# SDA381V5.net
KiCad netlist of a schematic drawn in EAGLE
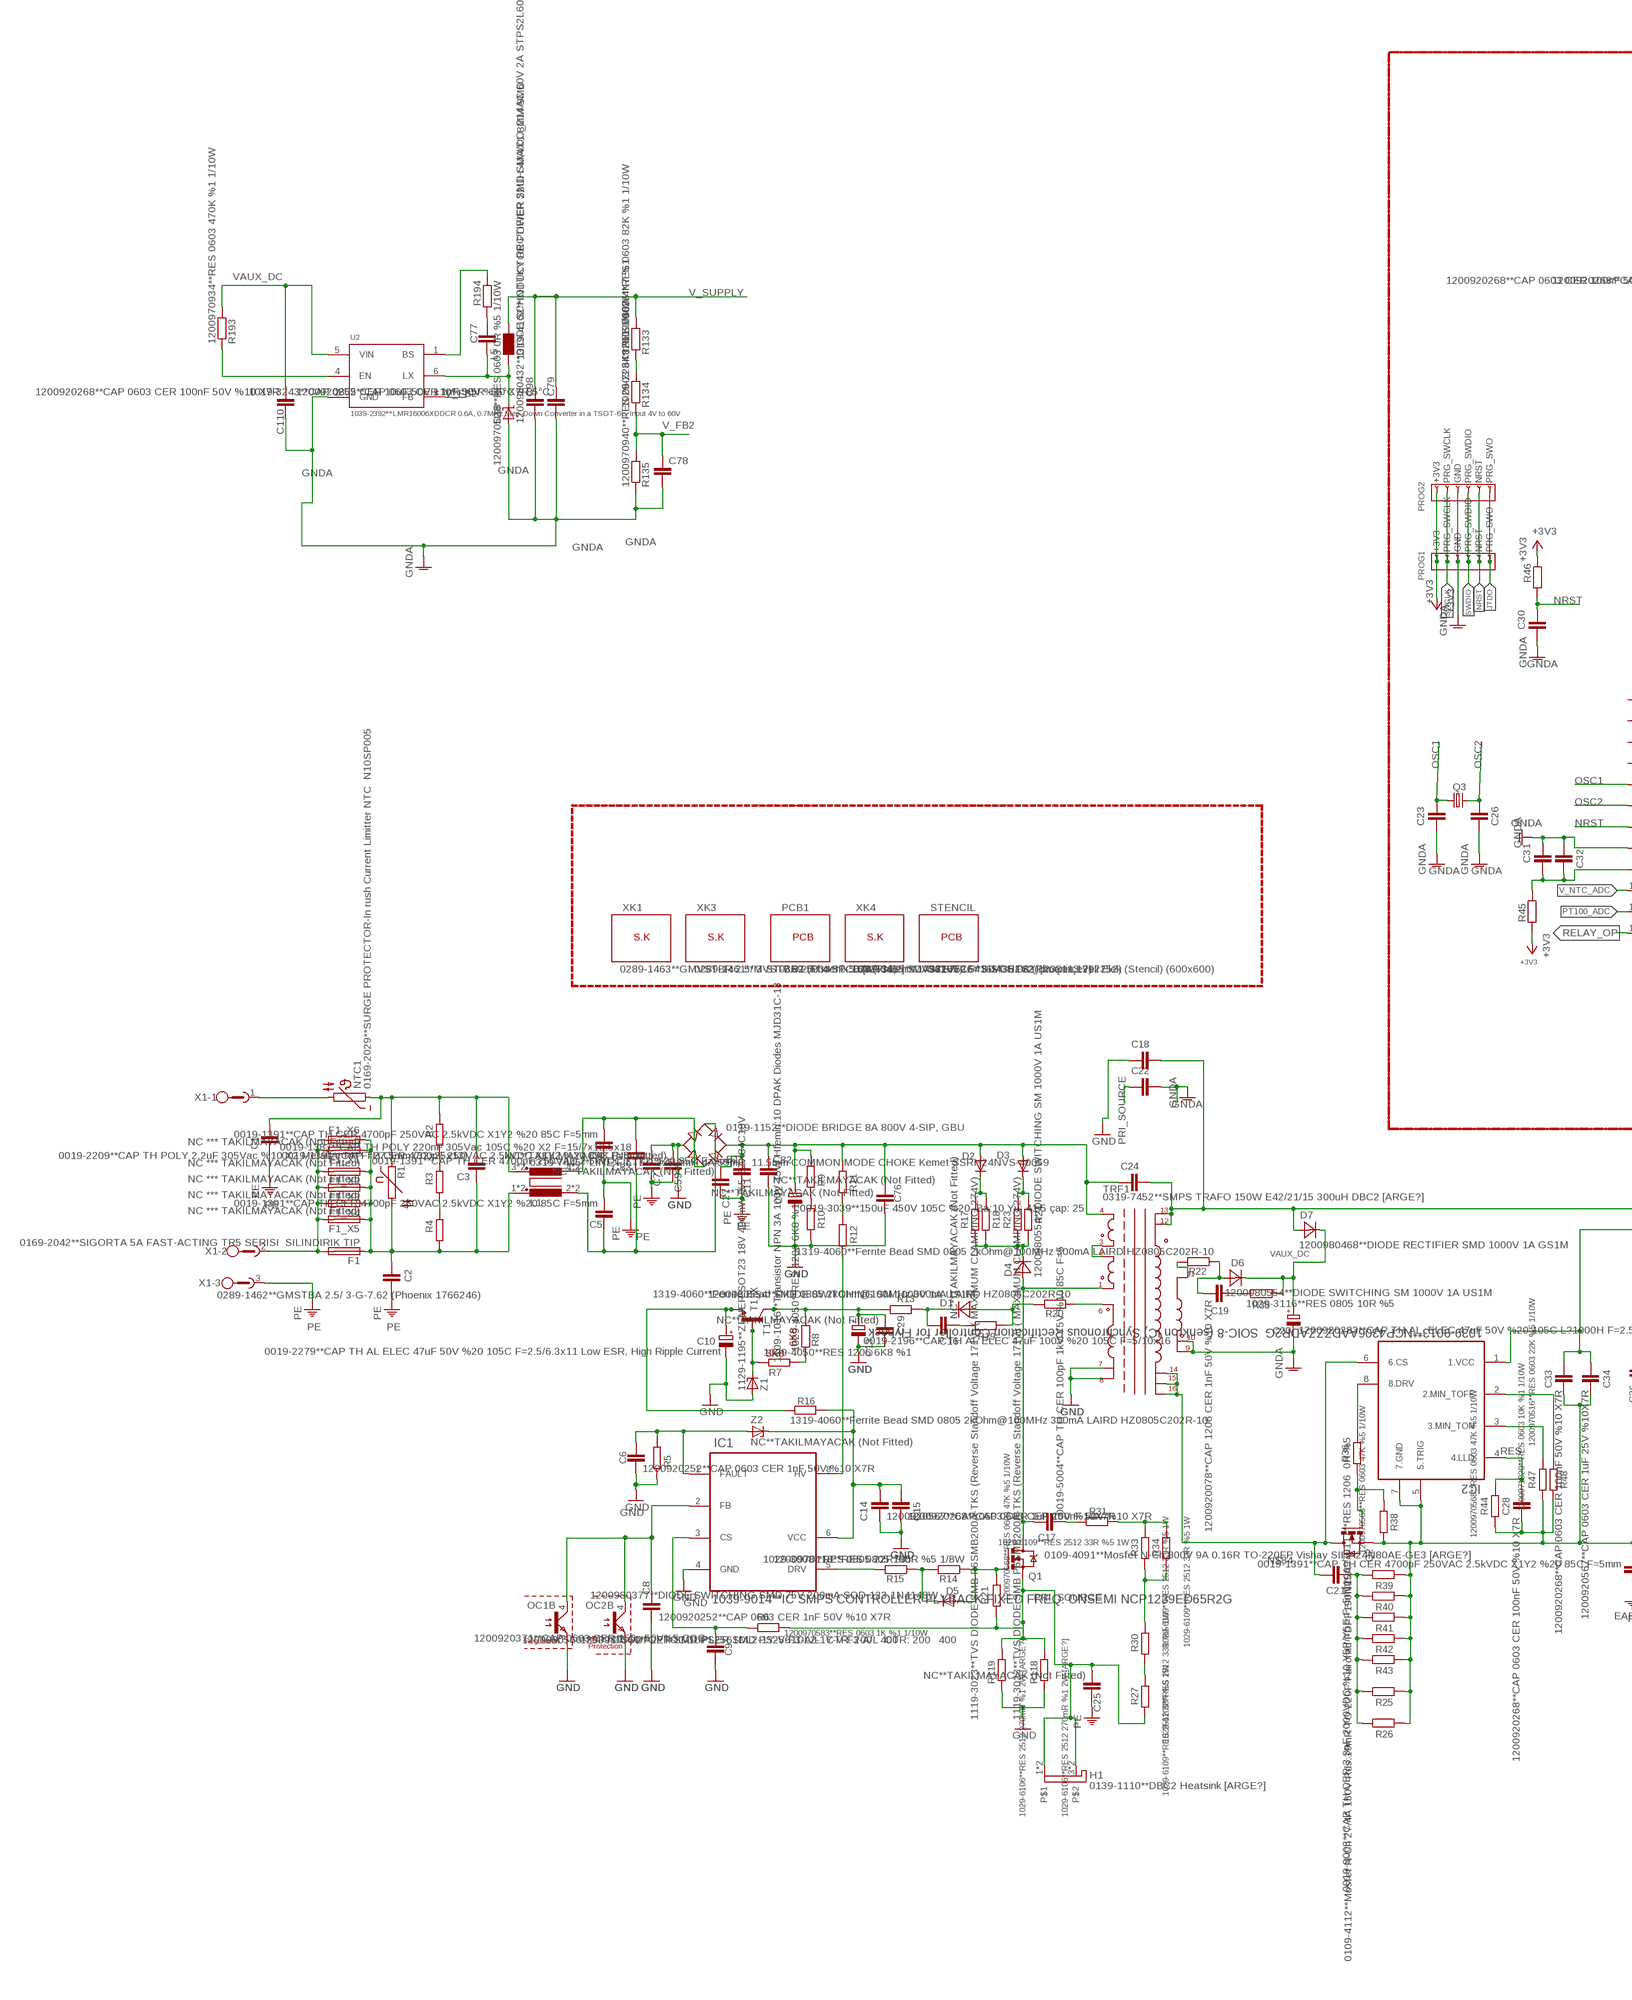
[diagram p0: schematic, sheet 1, part 1 of 2]
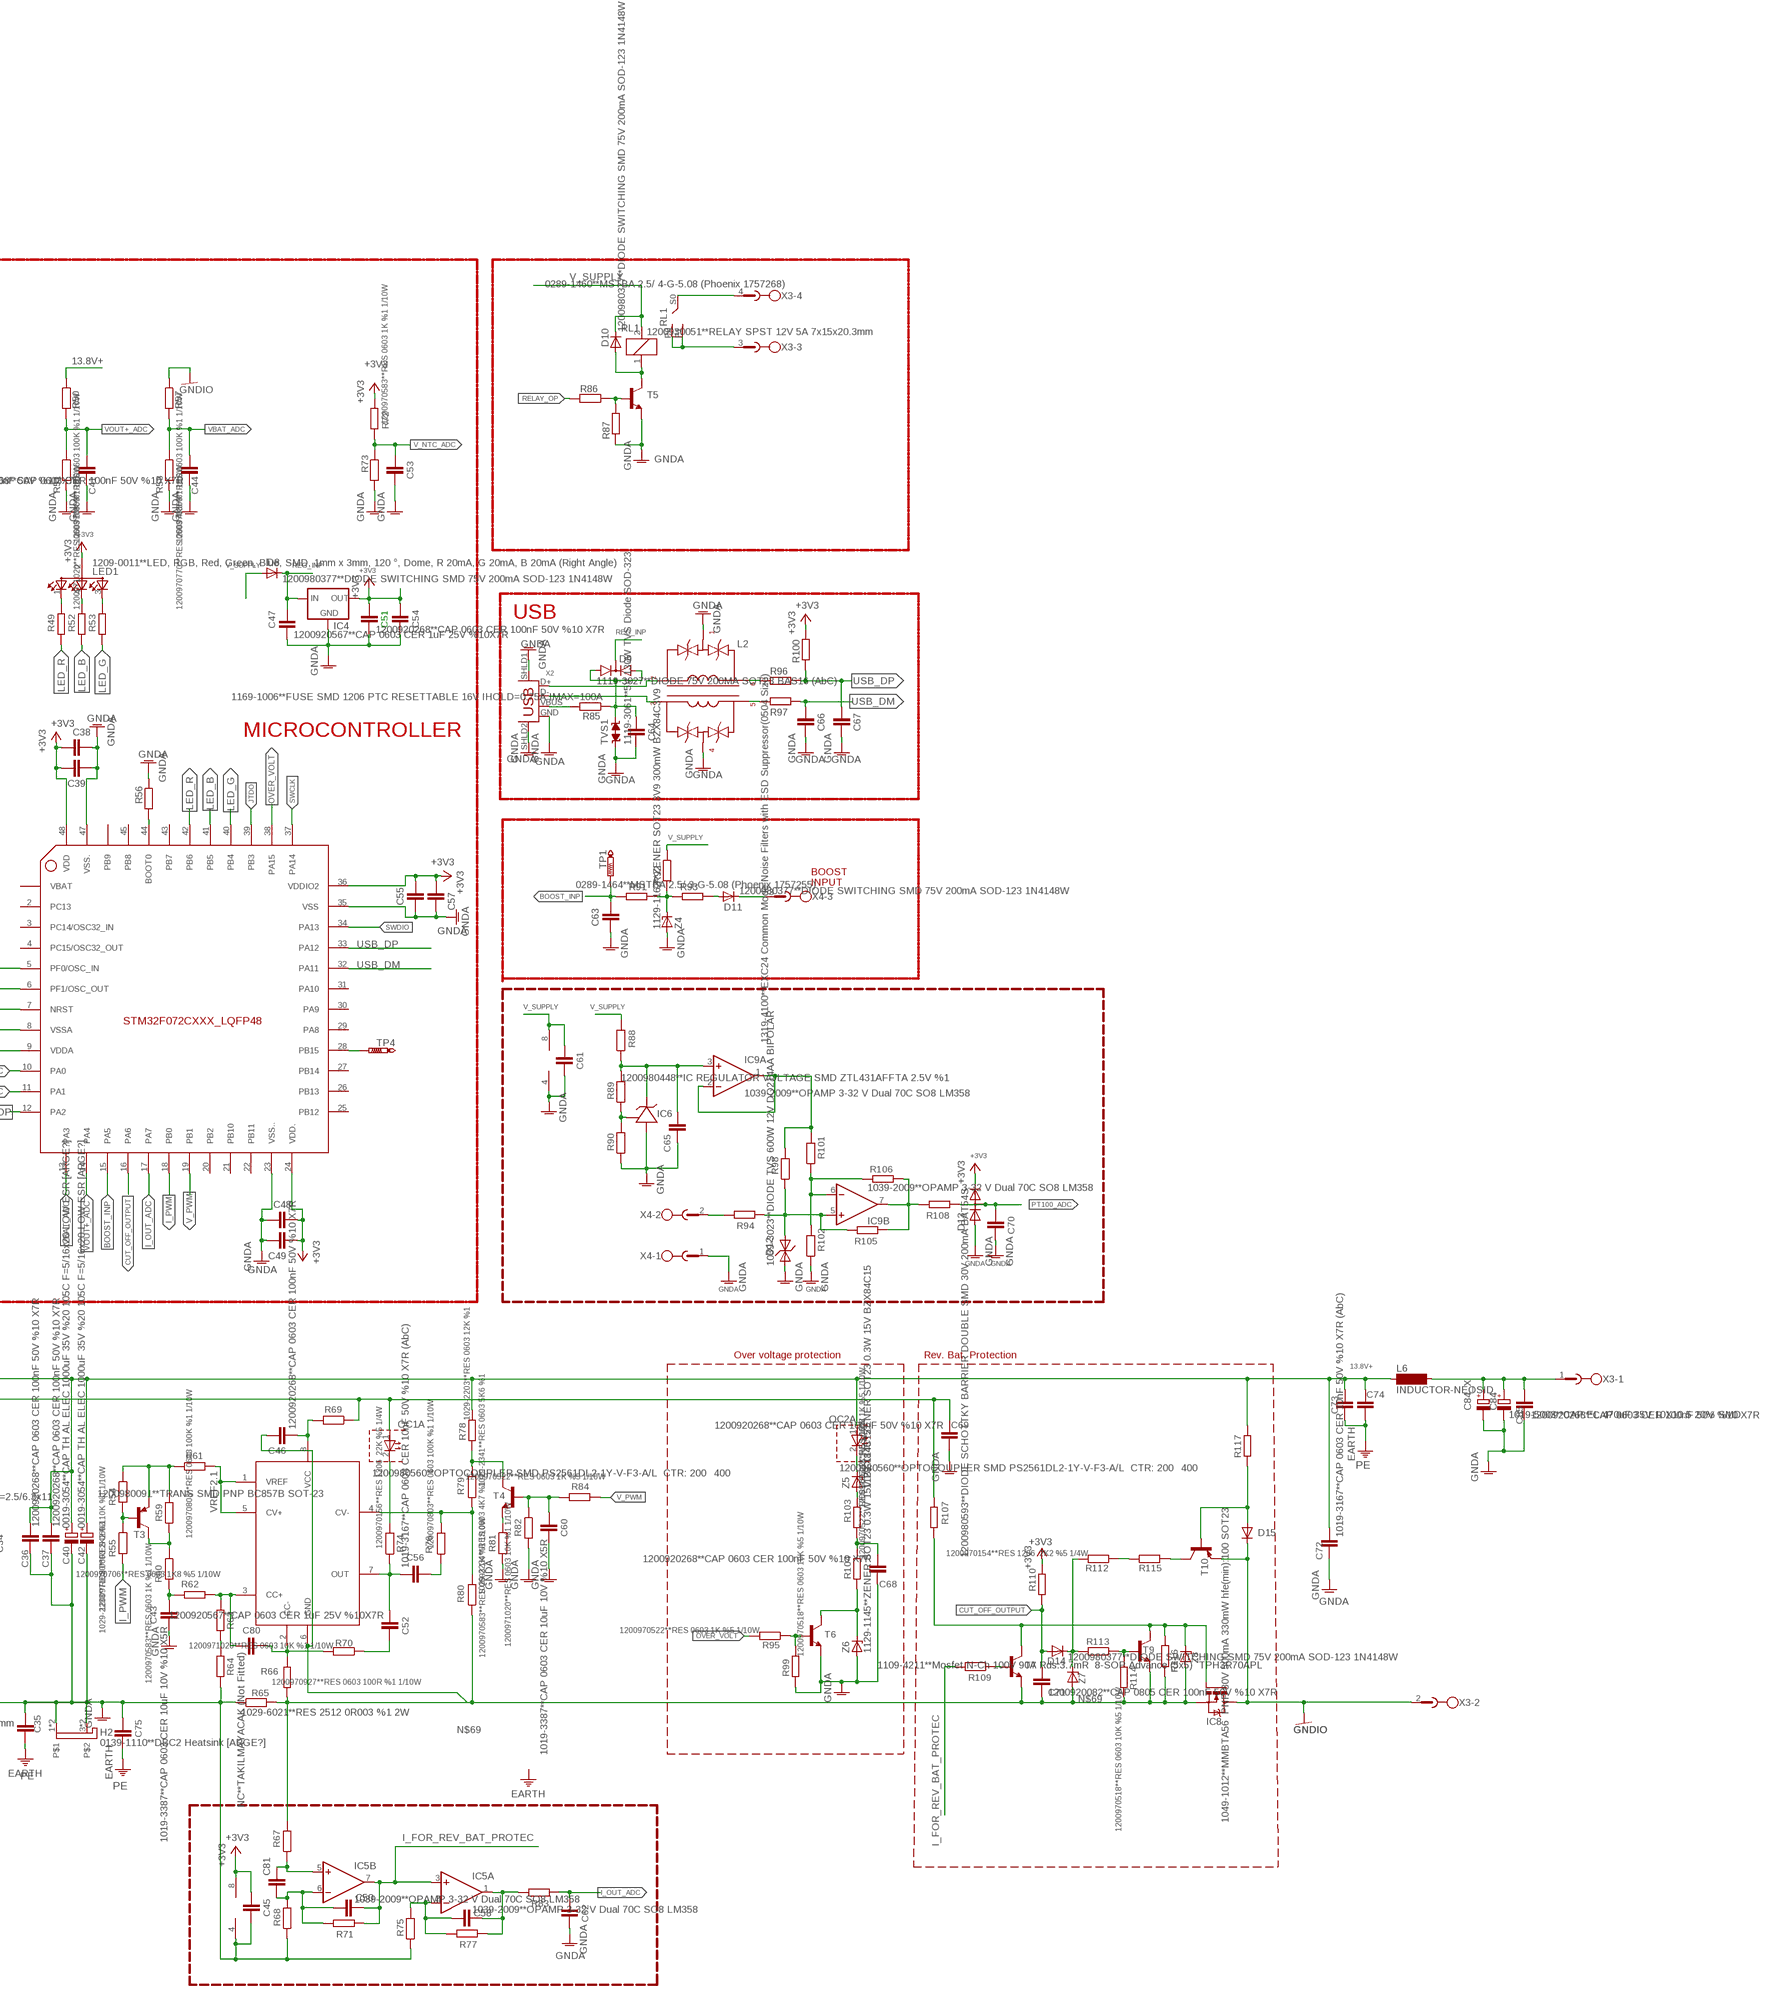
[diagram p1: schematic, sheet 1, part 2 of 2]

(export (version "E")
  (design (tool "Eeschema 10.0.6"))
  (components
    (comp (ref "B1")
      (value "0119-1152**DIODE BRIDGE 8A 800V 4-SIP, GBU")
      (footprint "eagle-import:DıODE_BRIDGE_8A_DIK")
      (libsource (lib "eagle-import") (part "DıODE_BRIDGE_8A_DIK"))
    )
    (comp (ref "C1")
      (value "NC**TAKILMAYACAK (Not Fitted)")
      (footprint "eagle-import:C50-035X75")
      (libsource (lib "eagle-import") (part "C50-035X75"))
    )
    (comp (ref "C2")
      (value "NC**TAKILMAYACAK (Not Fitted)")
      (footprint "eagle-import:C50-035X75")
      (libsource (lib "eagle-import") (part "C50-035X75"))
    )
    (comp (ref "C3")
      (value "0019-2209**CAP TH POLY 2.2uF 305Vac %10 X2 Metalize PP F=27.5mm (32x25x13)")
      (footprint "eagle-import:C275-113X316_&_C150-072X183_&_C225-113X268")
      (libsource (lib "eagle-import") (part "C275-113X316_&_C150-072X183_&_C225-113X268"))
    )
    (comp (ref "C4")
      (value "0019-1391**CAP TH CER 4700pF 250VAC 2.5kVDC X1Y2 %20 85C F=5mm")
      (footprint "eagle-import:C50-035X75")
      (libsource (lib "eagle-import") (part "C50-035X75"))
    )
    (comp (ref "C5")
      (value "0019-1391**CAP TH CER 4700pF 250VAC 2.5kVDC X1Y2 %20 85C F=5mm")
      (footprint "eagle-import:C50-035X75")
      (libsource (lib "eagle-import") (part "C50-035X75"))
    )
    (comp (ref "C6")
      (value "1200920252**CAP 0603 CER 1nF 50V %10 X7R")
      (footprint "eagle-import:C0603_ENKO")
      (libsource (lib "eagle-import") (part "C-EUC0603E"))
    )
    (comp (ref "C7")
      (value "0019-1391**CAP TH CER 4700pF 250VAC 2.5kVDC X1Y2 %20 85C F=5mm")
      (footprint "eagle-import:C50-035X75")
      (libsource (lib "eagle-import") (part "C50-035X75"))
    )
    (comp (ref "C8")
      (value "1200920252**CAP 0603 CER 1nF 50V %10 X7R")
      (footprint "eagle-import:C0603_ENKO")
      (libsource (lib "eagle-import") (part "C-EUC0603E"))
    )
    (comp (ref "C9")
      (value "1200920371**CAP 0603 CER 150p 50V%5 COG")
      (footprint "eagle-import:C0603_ENKO")
      (libsource (lib "eagle-import") (part "C-EUC0603E"))
    )
    (comp (ref "C10")
      (value "0019-2279**CAP TH AL ELEC 47uF 50V %20 105C F=2.5/6.3x11 Low ESR, High Ripple Current")
      (footprint "eagle-import:E2,5-7")
      (libsource (lib "eagle-import") (part "CPOL-EUE2.5-7"))
    )
    (comp (ref "C11")
      (value "0019-1391**CAP TH CER 4700pF 250VAC 2.5kVDC X1Y2 %20 85C F=5mm")
      (footprint "eagle-import:C50-035X75")
      (libsource (lib "eagle-import") (part "C50-035X75"))
    )
    (comp (ref "C12")
      (value "0019-3039**150uF 450V 105C %20 Ba:10 Yu: 41,5 çap: 25")
      (footprint "eagle-import:EB25D")
      (libsource (lib "eagle-import") (part "rcl_334_CPOL-EUE10-25"))
    )
    (comp (ref "C13")
      (value "0019-2196**CAP TH AL ELEC 47uF 100V %20 105C F=5/10x16")
      (footprint "eagle-import:E5-10,5")
      (libsource (lib "eagle-import") (part "CPOL-EUE5-10.5"))
    )
    (comp (ref "C14")
      (value "1200920567**CAP 0603 CER 1uF 25V %10X7R")
      (footprint "eagle-import:C0603_ENKO")
      (libsource (lib "eagle-import") (part "C-EUC0603E"))
    )
    (comp (ref "C15")
      (value "1200920268**CAP 0603 CER 100nF 50V %10 X7R")
      (footprint "eagle-import:C0603_ENKO")
      (libsource (lib "eagle-import") (part "C-EUC0603E"))
    )
    (comp (ref "C16")
      (value "NC**TAKILMAYACAK (Not Fitted)")
      (footprint "eagle-import:C1206_ENKO")
      (libsource (lib "eagle-import") (part "C-EUC1206E"))
    )
    (comp (ref "C17")
      (value "0019-5004**CAP TH CER 100pF 1kV Y5V %10 85C F=5")
      (footprint "eagle-import:C075-32X103_C050-035X75")
      (libsource (lib "eagle-import") (part "C075-32X103/C050-035X75"))
    )
    (comp (ref "C18")
      (value "1200920292**CAP TH CER 2.2nF 300Vac %20 X1Y2 F=7.5mm DxS(13x5)")
      (footprint "eagle-import:C075-32X103_DEIF")
      (libsource (lib "eagle-import") (part "C075-32X103_DEIF"))
    )
    (comp (ref "C19")
      (value "1200920078**CAP 1206 CER 1nF 50V %10 X7R")
      (footprint "eagle-import:C1206_ENKO")
      (libsource (lib "eagle-import") (part "C-EUC1206E"))
    )
    (comp (ref "C20")
      (value "1200920283**CAP TH AL. ELEC 47uF 50V %20 105C L?1000H F=2.5/6.3x11")
      (footprint "eagle-import:E2,5-7")
      (libsource (lib "eagle-import") (part "rcl_334_CPOL-EUE2.5-7"))
    )
    (comp (ref "C21")
      (value "0019-3003**CAP TH CER 3.3nF 2000VDC %10 Y5P/Y5E F=5mm")
      (footprint "eagle-import:C050-045X075")
      (libsource (lib "eagle-import") (part "C-EU050-045X075"))
    )
    (comp (ref "C22")
      (value "NC**TAKILMAYACAK (Not Fitted)")
      (footprint "eagle-import:C075-32X103_DEIF")
      (libsource (lib "eagle-import") (part "C075-32X103_DEIF"))
    )
    (comp (ref "C23")
      (value "1019-3352**CAP 0603 CER 22pF 50V %5 NPO")
      (footprint "eagle-import:C0603_ENKO")
      (libsource (lib "eagle-import") (part "C-EUC0603E"))
    )
    (comp (ref "C24")
      (value "NC**TAKILMAYACAK (Not Fitted)")
      (footprint "eagle-import:C075-32X103_DEIF")
      (libsource (lib "eagle-import") (part "C075-32X103_DEIF"))
    )
    (comp (ref "C25")
      (value "NC**TAKILMAYACAK (Not Fitted)")
      (footprint "eagle-import:C50-035X75")
      (libsource (lib "eagle-import") (part "C50-035X75"))
    )
    (comp (ref "C26")
      (value "1019-3352**CAP 0603 CER 22pF 50V %5 NPO")
      (footprint "eagle-import:C0603_ENKO")
      (libsource (lib "eagle-import") (part "C-EUC0603E"))
    )
    (comp (ref "C27")
      (value "NC**TAKILMAYACAK (Not Fitted)")
      (footprint "eagle-import:C50-035X75")
      (libsource (lib "eagle-import") (part "C50-035X75"))
    )
    (comp (ref "C28")
      (value "1200920268**CAP 0603 CER 100nF 50V %10 X7R")
      (footprint "eagle-import:C0603_ENKO")
      (libsource (lib "eagle-import") (part "C-EUC0603E"))
    )
    (comp (ref "C29")
      (value "NC**TAKILMAYACAK (Not Fitted)")
      (footprint "eagle-import:C1206_ENKO")
      (libsource (lib "eagle-import") (part "C-EUC1206E"))
    )
    (comp (ref "C30")
      (value "1200920268**CAP 0603 CER 100nF 50V %10 X7R")
      (footprint "eagle-import:C0603_ENKO")
      (libsource (lib "eagle-import") (part "C-EUC0603E"))
    )
    (comp (ref "C31")
      (value "1200920268**CAP 0603 CER 100nF 50V %10 X7R")
      (footprint "eagle-import:C0603_ENKO")
      (libsource (lib "eagle-import") (part "C-EUC0603E"))
    )
    (comp (ref "C32")
      (value "1019-3167**CAP 0603 CER 10nF 50V %10 X7R (AbC)")
      (footprint "eagle-import:C0603_ENKO")
      (libsource (lib "eagle-import") (part "C-EUC0603E"))
    )
    (comp (ref "C33")
      (value "1200920268**CAP 0603 CER 100nF 50V %10 X7R")
      (footprint "eagle-import:C0603_ENKO")
      (libsource (lib "eagle-import") (part "C-EUC0603E"))
    )
    (comp (ref "C34")
      (value "1200920567**CAP 0603 CER 1uF 25V %10X7R")
      (footprint "eagle-import:C0603_ENKO")
      (libsource (lib "eagle-import") (part "C-EUC0603E"))
    )
    (comp (ref "C35")
      (value "0019-1391**CAP TH CER 4700pF 250VAC 2.5kVDC X1Y2 %20 85C F=5mm")
      (footprint "eagle-import:C050-045X075")
      (libsource (lib "eagle-import") (part "C-EU050-045X075"))
    )
    (comp (ref "C36")
      (value "1200920268**CAP 0603 CER 100nF 50V %10 X7R")
      (footprint "eagle-import:C0603_ENKO")
      (libsource (lib "eagle-import") (part "C-EUC0603E"))
    )
    (comp (ref "C37")
      (value "1200920268**CAP 0603 CER 100nF 50V %10 X7R")
      (footprint "eagle-import:C0603_ENKO")
      (libsource (lib "eagle-import") (part "C-EUC0603E"))
    )
    (comp (ref "C38")
      (value "1200920268**CAP 0603 CER 100nF 50V %10 X7R")
      (footprint "eagle-import:C0603_ENKO")
      (libsource (lib "eagle-import") (part "C-EUC0603E"))
    )
    (comp (ref "C39")
      (value "1019-3167**CAP 0603 CER 10nF 50V %10 X7R (AbC)")
      (footprint "eagle-import:C0603_ENKO")
      (libsource (lib "eagle-import") (part "C-EUC0603E"))
    )
    (comp (ref "C40")
      (value "0019-3054**CAP TH AL ELEC 1000uF 35V %20 105C F=5/16x20 LOW ESR [ARGE?]")
      (footprint "eagle-import:E5-13_E7,5-16")
      (libsource (lib "eagle-import") (part "E5-13/E7,5-16"))
    )
    (comp (ref "C41")
      (value "1200920268**CAP 0603 CER 100nF 50V %10 X7R")
      (footprint "eagle-import:C0603_ENKO")
      (libsource (lib "eagle-import") (part "C-EUC0603E"))
    )
    (comp (ref "C42")
      (value "0019-3054**CAP TH AL ELEC 1000uF 35V %20 105C F=5/16x20 LOW ESR [ARGE?]")
      (footprint "eagle-import:E5-13")
      (libsource (lib "eagle-import") (part "CPOL-EUE5-13"))
    )
    (comp (ref "C43")
      (value "1019-3387**CAP 0603 CER 10uF 10V %10 X5R")
      (footprint "eagle-import:C0603_ENKO")
      (libsource (lib "eagle-import") (part "C-EUC0603E"))
    )
    (comp (ref "C44")
      (value "1200920268**CAP 0603 CER 100nF 50V %10 X7R")
      (footprint "eagle-import:C0603_ENKO")
      (libsource (lib "eagle-import") (part "C-EUC0603E"))
    )
    (comp (ref "C45")
      (value "1200920268**CAP 0603 CER 100nF 50V %10 X7R")
      (footprint "eagle-import:C0603_ENKO")
      (libsource (lib "eagle-import") (part "C-EUC0603E"))
    )
    (comp (ref "C46")
      (value "1200920268**CAP 0603 CER 100nF 50V %10 X7R")
      (footprint "eagle-import:C0603_ENKO")
      (libsource (lib "eagle-import") (part "C-EUC0603E"))
    )
    (comp (ref "C47")
      (value "1200920567**CAP 0603 CER 1uF 25V %10X7R")
      (footprint "eagle-import:C0603_ENKO")
      (libsource (lib "eagle-import") (part "C-EUC0603E"))
    )
    (comp (ref "C48")
      (value "1019-3167**CAP 0603 CER 10nF 50V %10 X7R (AbC)")
      (footprint "eagle-import:C0603_ENKO")
      (libsource (lib "eagle-import") (part "C-EUC0603E"))
    )
    (comp (ref "C49")
      (value "1200920268**CAP 0603 CER 100nF 50V %10 X7R")
      (footprint "eagle-import:C0603_ENKO")
      (libsource (lib "eagle-import") (part "C-EUC0603E"))
    )
    (comp (ref "C50")
      (value "NC**TAKILMAYACAK (Not Fitted)")
      (footprint "eagle-import:C0603_ENKO")
      (libsource (lib "eagle-import") (part "C-EUC0603E"))
    )
    (comp (ref "C51")
      (value "1200920268**CAP 0603 CER 100nF 50V %10 X7R")
      (footprint "eagle-import:C0603_ENKO")
      (libsource (lib "eagle-import") (part "C-EUC0603E"))
    )
    (comp (ref "C52")
      (value "1200920567**CAP 0603 CER 1uF 25V %10X7R")
      (footprint "eagle-import:C0603_ENKO")
      (libsource (lib "eagle-import") (part "C-EUC0603E"))
    )
    (comp (ref "C53")
      (value "1200920268**CAP 0603 CER 100nF 50V %10 X7R")
      (footprint "eagle-import:C0603_ENKO")
      (libsource (lib "eagle-import") (part "C-EUC0603E"))
    )
    (comp (ref "C54")
      (value "1019-3301**CAP 0805 47uF 6.3V %20 X5R")
      (footprint "eagle-import:C0805_ENKO")
      (libsource (lib "eagle-import") (part "C-EUC0805E"))
    )
    (comp (ref "C55")
      (value "1019-3167**CAP 0603 CER 10nF 50V %10 X7R (AbC)")
      (footprint "eagle-import:C0603_ENKO")
      (libsource (lib "eagle-import") (part "C-EUC0603E"))
    )
    (comp (ref "C56")
      (value "1019-3167**CAP 0603 CER 10nF 50V %10 X7R (AbC)")
      (footprint "eagle-import:C0603_ENKO")
      (libsource (lib "eagle-import") (part "C-EUC0603E"))
    )
    (comp (ref "C57")
      (value "1200920268**CAP 0603 CER 100nF 50V %10 X7R")
      (footprint "eagle-import:C0603_ENKO")
      (libsource (lib "eagle-import") (part "C-EUC0603E"))
    )
    (comp (ref "C58")
      (value "1200920371**CAP 0603 CER 150p 50V%5 COG")
      (footprint "eagle-import:C0603_ENKO")
      (libsource (lib "eagle-import") (part "C-EUC0603E"))
    )
    (comp (ref "C59")
      (value "NC**TAKILMAYACAK (Not Fitted)")
      (footprint "eagle-import:C50-035X75")
      (libsource (lib "eagle-import") (part "C50-035X75"))
    )
    (comp (ref "C60")
      (value "1019-3387**CAP 0603 CER 10uF 10V %10 X5R")
      (footprint "eagle-import:C0603_ENKO")
      (libsource (lib "eagle-import") (part "C-EUC0603E"))
    )
    (comp (ref "C61")
      (value "1200920268**CAP 0603 CER 100nF 50V %10 X7R")
      (footprint "eagle-import:C0603_ENKO")
      (libsource (lib "eagle-import") (part "C-EUC0603E"))
    )
    (comp (ref "C62")
      (value "1200920268**CAP 0603 CER 100nF 50V %10 X7R")
      (footprint "eagle-import:C0603_ENKO")
      (libsource (lib "eagle-import") (part "C-EUC0603E"))
    )
    (comp (ref "C63")
      (value "1019-3167**CAP 0603 CER 10nF 50V %10 X7R (AbC)")
      (footprint "eagle-import:C0603_ENKO")
      (libsource (lib "eagle-import") (part "C-EUC0603E"))
    )
    (comp (ref "C64")
      (value "1200920268**CAP 0603 CER 100nF 50V %10 X7R")
      (footprint "eagle-import:C0603_ENKO")
      (libsource (lib "eagle-import") (part "C-EUC0603E"))
    )
    (comp (ref "C65")
      (value "1200920268**CAP 0603 CER 100nF 50V %10 X7R")
      (footprint "eagle-import:C0603_ENKO")
      (libsource (lib "eagle-import") (part "C-EUC0603E"))
    )
    (comp (ref "C66")
      (value "1019-3381**CAP 0603 CER 33pf 50V %5 NPO(COG)")
      (footprint "eagle-import:C0603_ENKO")
      (libsource (lib "eagle-import") (part "C-EUC0603E"))
    )
    (comp (ref "C67")
      (value "1019-3381**CAP 0603 CER 33pf 50V %5 NPO(COG)")
      (footprint "eagle-import:C0603_ENKO")
      (libsource (lib "eagle-import") (part "C-EUC0603E"))
    )
    (comp (ref "C68")
      (value "1200920268**CAP 0603 CER 100nF 50V %10 X7R")
      (footprint "eagle-import:C0603_ENKO")
      (libsource (lib "eagle-import") (part "C-EUC0603E"))
    )
    (comp (ref "C69")
      (value "1200920268**CAP 0603 CER 100nF 50V %10 X7R")
      (footprint "eagle-import:C0603_ENKO")
      (libsource (lib "eagle-import") (part "C-EUC0603E"))
    )
    (comp (ref "C70")
      (value "1200920268**CAP 0603 CER 100nF 50V %10 X7R")
      (footprint "eagle-import:C0603_ENKO")
      (libsource (lib "eagle-import") (part "C-EUC0603E"))
    )
    (comp (ref "C71")
      (value "1200920082**CAP 0805 CER 100nF 50V %10 X7R")
      (footprint "eagle-import:C0805_ENKO")
      (libsource (lib "eagle-import") (part "C-EUC0805E"))
    )
    (comp (ref "C72")
      (value "1019-3167**CAP 0603 CER 10nF 50V %10 X7R (AbC)")
      (footprint "eagle-import:C0603_ENKO")
      (libsource (lib "eagle-import") (part "C-EUC0603E"))
    )
    (comp (ref "C73")
      (value "0019-1391**CAP TH CER 4700pF 250VAC 2.5kVDC X1Y2 %20 85C F=5mm")
      (footprint "eagle-import:C050-035X075")
      (libsource (lib "eagle-import") (part "C-EU050-035X075"))
    )
    (comp (ref "C74")
      (value "NC**TAKILMAYACAK (Not Fitted)")
      (footprint "eagle-import:C050-035X075")
      (libsource (lib "eagle-import") (part "C-EU050-035X075"))
    )
    (comp (ref "C75")
      (value "NC**TAKILMAYACAK (Not Fitted)")
      (footprint "eagle-import:C050-035X075")
      (libsource (lib "eagle-import") (part "C-EU050-035X075"))
    )
    (comp (ref "C76")
      (value "NC**TAKILMAYACAK (Not Fitted)")
      (footprint "eagle-import:C065-052X106")
      (libsource (lib "eagle-import") (part "C065-052X106"))
    )
    (comp (ref "C77")
      (value "1200920268**CAP 0603 CER 100nF 50V %10 X7R")
      (footprint "eagle-import:C0603_ENKO")
      (libsource (lib "eagle-import") (part "C-EUC0603E"))
    )
    (comp (ref "C78")
      (value "1200920271**CAP 0603 CER 10pF 50V%10 COG")
      (footprint "eagle-import:C0603_ENKO")
      (libsource (lib "eagle-import") (part "C-EUC0603E"))
    )
    (comp (ref "C79")
      (value "1019-3243**CAP 0805 CER 10uF 50V ±10% X5R -55°C ~ 85°C")
      (footprint "eagle-import:C0805_ENKO")
      (libsource (lib "eagle-import") (part "C-EUC0805E"))
    )
    (comp (ref "C80")
      (value "NC**TAKILMAYACAK (Not Fitted)")
      (footprint "eagle-import:C0603_ENKO")
      (libsource (lib "eagle-import") (part "C-EUC0603E"))
    )
    (comp (ref "C81")
      (value "NC**TAKILMAYACAK (Not Fitted)")
      (footprint "eagle-import:C0603_ENKO")
      (libsource (lib "eagle-import") (part "C-EUC0603E"))
    )
    (comp (ref "C82")
      (value "NC**TAKILMAYACAK (Not Fitted)")
      (footprint "eagle-import:C150-091X182")
      (libsource (lib "eagle-import") (part "C-EU150-091X182"))
    )
    (comp (ref "C83")
      (value "0019-1383**CAP TH POLY 220nF 305Vac 105C %20 X2 F=15/7x13.5x18")
      (footprint "eagle-import:C150-091X182_C225-108X268")
      (libsource (lib "eagle-import") (part "C150-091X182_C225-108X268"))
    )
    (comp (ref "C84")
      (value "1019-5003**CAP.EL.470uF 35V 10X10.5 20% SMD")
      (footprint "eagle-import:E5-10,5")
      (libsource (lib "eagle-import") (part "CPOL-EUE5-10.5"))
    )
    (comp (ref "C84_X")
      (value "CPOL-EUE2.5-7")
      (footprint "eagle-import:E2,5-7")
      (libsource (lib "eagle-import") (part "CPOL-EUE2.5-7"))
    )
    (comp (ref "C85")
      (value "1200920268**CAP 0603 CER 100nF 50V %10 X7R")
      (footprint "eagle-import:C0603_ENKO")
      (libsource (lib "eagle-import") (part "C-EUC0603E"))
    )
    (comp (ref "C98")
      (value "1200920252**CAP 0603 CER 1nF 50V %10 X7R")
      (footprint "eagle-import:C0603_ENKO")
      (libsource (lib "eagle-import") (part "C-EUC0603E"))
    )
    (comp (ref "C110")
      (value "1200920268**CAP 0603 CER 100nF 50V %10 X7R")
      (footprint "eagle-import:C0603_ENKO")
      (libsource (lib "eagle-import") (part "C-EUC0603E"))
    )
    (comp (ref "D1")
      (value "1200980554**DIODE SWITCHING SM 1000V 1A US1M")
      (footprint "eagle-import:M7_DC_DIYOT")
      (libsource (lib "eagle-import") (part "M7_DC_DIYOT"))
    )
    (comp (ref "D2")
      (value "1119-3023**TVS DIODE SMB P6SMB200A-TKS (Reverse Standoff Voltage 171V) ( MAXIMUM CLAMPING 274V)")
      (footprint "eagle-import:SMB")
      (libsource (lib "eagle-import") (part "DIODE-SMB"))
    )
    (comp (ref "D3")
      (value "1119-3023**TVS DIODE SMB P6SMB200A-TKS (Reverse Standoff Voltage 171V) ( MAXIMUM CLAMPING 274V)")
      (footprint "eagle-import:SMB")
      (libsource (lib "eagle-import") (part "DIODE-SMB"))
    )
    (comp (ref "D4")
      (value "1200980554**DIODE SWITCHING SM 1000V 1A US1M")
      (footprint "eagle-import:M7_DC_DIYOT")
      (libsource (lib "eagle-import") (part "M7_DC_DIYOT"))
    )
    (comp (ref "D5")
      (value "1200980377**DIODE SWITCHING SMD 75V 200mA SOD-123 1N4148W")
      (footprint "eagle-import:SOD123")
      (libsource (lib "eagle-import") (part "DIODE-SOD123"))
    )
    (comp (ref "D6")
      (value "1200980554**DIODE SWITCHING SM 1000V 1A US1M")
      (footprint "eagle-import:M7_DC_DIYOT")
      (libsource (lib "eagle-import") (part "M7_DC_DIYOT"))
    )
    (comp (ref "D7")
      (value "1200980468**DIODE RECTIFIER SMD 1000V 1A GS1M")
      (footprint "eagle-import:M7_DC_DIYOT")
      (libsource (lib "eagle-import") (part "M7_DC_DIYOT"))
    )
    (comp (ref "D8")
      (value "1200980377**DIODE SWITCHING SMD 75V 200mA SOD-123 1N4148W")
      (footprint "eagle-import:SOD123")
      (libsource (lib "eagle-import") (part "DIODE-SOD123"))
    )
    (comp (ref "D9")
      (value "1119-3027**DIODE 75V 200MA SOT23 BAS16 (AbC)")
      (footprint "eagle-import:SOT23")
      (libsource (lib "eagle-import") (part "DIODE-2AC|CASOT23"))
    )
    (comp (ref "D10")
      (value "1200980377**DIODE SWITCHING SMD 75V 200mA SOD-123 1N4148W")
      (footprint "eagle-import:SOD123")
      (libsource (lib "eagle-import") (part "DIODE-SOD123"))
    )
    (comp (ref "D11")
      (value "1200980377**DIODE SWITCHING SMD 75V 200mA SOD-123 1N4148W")
      (footprint "eagle-import:SOD123")
      (libsource (lib "eagle-import") (part "DIODE-SOD123"))
    )
    (comp (ref "D12")
      (value "1039-3023**DIODE TVS 600W 12V DO214AA BIPOLAR")
      (footprint "eagle-import:TRANSIL_SMB")
      (libsource (lib "eagle-import") (part "TRANSIL_SMB"))
    )
    (comp (ref "D13")
      (value "1200980593**DIODE SCHOTTKY BARRIER DOUBLE SMD 30V 200mA BAT54S")
      (footprint "eagle-import:SOT23")
      (libsource (lib "eagle-import") (part "BAV199"))
    )
    (comp (ref "D14")
      (value "1200980377**DIODE SWITCHING SMD 75V 200mA SOD-123 1N4148W")
      (footprint "eagle-import:SOD123")
      (libsource (lib "eagle-import") (part "DIODE-SOD123"))
    )
    (comp (ref "D15")
      (value "1200980377**DIODE SWITCHING SMD 75V 200mA SOD-123 1N4148W")
      (footprint "eagle-import:SOD123")
      (libsource (lib "eagle-import") (part "DIODE-SOD123"))
    )
    (comp (ref "D18")
      (value "1200980432**DIODE SCHOTTKY RECTIFIER SMD SMA/DO_214AC 60V 2A STPS2L60A")
      (footprint "eagle-import:SMA")
      (libsource (lib "eagle-import") (part "SD-SMA"))
    )
    (comp (ref "F1")
      (value "0169-2042**SIGORTA 5A FAST-ACTING TR5 SERISI SILINDIRIK TIP")
      (footprint "eagle-import:SENS_FUSE")
      (libsource (lib "eagle-import") (part "SENS_FUSE"))
    )
    (comp (ref "F1_X1")
      (value "NC *** TAKILMAYACAK (Not Fitted)")
      (footprint "eagle-import:FUSE_0678D")
      (libsource (lib "eagle-import") (part "FUSE_0678D"))
    )
    (comp (ref "F1_X2")
      (value "NC *** TAKILMAYACAK (Not Fitted)")
      (footprint "eagle-import:FUSE_1025FA")
      (libsource (lib "eagle-import") (part "FUSE_1025FA"))
    )
    (comp (ref "F1_X3")
      (value "NC *** TAKILMAYACAK (Not Fitted)")
      (footprint "eagle-import:FUSE_EBF_FUSE_446_447")
      (libsource (lib "eagle-import") (part "FUSE_EBF_FUSE_446/447"))
    )
    (comp (ref "F1_X4")
      (value "NC *** TAKILMAYACAK (Not Fitted)")
      (footprint "eagle-import:FUSE_OMF250")
      (libsource (lib "eagle-import") (part "FUSE_OMF250"))
    )
    (comp (ref "F1_X5")
      (value "NC *** TAKILMAYACAK (Not Fitted)")
      (footprint "eagle-import:FUSE_UMF250")
      (libsource (lib "eagle-import") (part "FUSE_UMF250"))
    )
    (comp (ref "F1_X6")
      (value "FUSE_TYPE0679H")
      (footprint "eagle-import:FUSE_TYPE0679H")
      (libsource (lib "eagle-import") (part "FUSE_TYPE0679H"))
    )
    (comp (ref "H1")
      (value "0139-1110**DBC2 Heatsink [ARGE?]")
      (footprint "eagle-import:DEIF_SOGUTUCU_2")
      (libsource (lib "eagle-import") (part "DEIF_SOGUTUCU_2"))
    )
    (comp (ref "H2")
      (value "0139-1110**DBC2 Heatsink [ARGE?]")
      (footprint "eagle-import:DEIF_SOGUTUCU_2")
      (libsource (lib "eagle-import") (part "DEIF_SOGUTUCU_2"))
    )
    (comp (ref "IC1")
      (value "1039-9014**IC SMPS CONTROLLER FLYBACK FIXED FREQ. ONSEMI NCP1239ED65R2G")
      (footprint "eagle-import:NCP1239_SMPS_IC")
      (libsource (lib "eagle-import") (part "NCP1239_SMPS_IC"))
    )
    (comp (ref "IC2")
      (value "1039-9013**NCP4306AADZZZADR2G SOIC-8 (senkron IC) Synchronous Rectification Controller for Flyback")
      (footprint "eagle-import:NCP4306")
      (libsource (lib "eagle-import") (part "NCP4306"))
    )
    (comp (ref "IC3")
      (value "1039-2224**TSM1011ID SO-8 Constant Voltage and Constant Current Controller")
      (footprint "eagle-import:SO-8")
      (libsource (lib "eagle-import") (part "TSM1011"))
    )
    (comp (ref "IC4")
      (value "1039-3003**Voltage Regulator SOT-89 3.3V Diodes AP2204RA-3.3TRG1")
      (footprint "eagle-import:SOT89")
      (libsource (lib "eagle-import") (part "S-812XSGUP"))
    )
    (comp (ref "IC5")
      (value "1039-2009**OPAMP 3-32 V Dual 70C SO8 LM358")
      (footprint "eagle-import:SO08")
      (libsource (lib "eagle-import") (part "LM358D"))
    )
    (comp (ref "IC6")
      (value "1200980448**IC REGULATOR VOLTAGE SMD ZTL431AFFTA 2.5V %1")
      (footprint "eagle-import:TL431_SOT23F")
      (libsource (lib "eagle-import") (part "TL431_SOT23F"))
    )
    (comp (ref "IC8")
      (value "1109-4211**Mosfet N-Ch 100V 90A Rds:3.7mR 8-SOP Advance (5x5) TPH3R70APL")
      (footprint "eagle-import:TPH6R30ANL")
      (libsource (lib "eagle-import") (part "TPH6R30ANL"))
    )
    (comp (ref "IC9")
      (value "1039-2009**OPAMP 3-32 V Dual 70C SO8 LM358")
      (footprint "eagle-import:SO08")
      (libsource (lib "eagle-import") (part "LM358D"))
    )
    (comp (ref "L1")
      (value "0319-7445**LINE FILTER 2x5,9mH 4A 55mR 11.5mm COMMON MODE CHOKE Kemet SSRH24NVS-40059")
      (footprint "eagle-import:UU1620_&_FWCMET24V")
      (libsource (lib "eagle-import") (part "UU1620_&_FWCMET24V"))
    )
    (comp (ref "L2")
      (value "1319-4100**EXC24 Common Mode Noise Filters with ESD Suppressor(0504 Size)")
      (footprint "eagle-import:EXC24CS_COMMON_MODE")
      (libsource (lib "eagle-import") (part "EXC24CS_COMMON_MODE"))
    )
    (comp (ref "L5")
      (value "1319-4102**INDUCTOR POWER 22UH 4X4X1.8MM SMD")
      (footprint "eagle-import:WE-PD2_5MM")
      (libsource (lib "eagle-import") (part "WE-PD2WE_PD2_5MM"))
    )
    (comp (ref "L6")
      (value "INDUCTOR-NEOSID")
      (footprint "eagle-import:INDUCTOR-NEOSID")
      (libsource (lib "eagle-import") (part "INDUCTOR-NEOSID"))
    )
    (comp (ref "LED1")
      (value "1209-0011**LED, RGB, Red, Green, Blue, SMD, 1mm x 3mm, 120 °, Dome, R 20mA, G 20mA, B 20mA (Right Angle)")
      (footprint "eagle-import:KPFA-3010RGBC-11")
      (libsource (lib "eagle-import") (part "KPFA-3010RGBC-11"))
    )
    (comp (ref "NTC1")
      (value "0169-2029**SURGE PROTECTOR-In rush Current Limitter NTC N10SP005")
      (footprint "eagle-import:NTC_15R_2A_&_N15SP005-5")
      (libsource (lib "eagle-import") (part "NTC_15R_2A_&_N15SP005-5"))
    )
    (comp (ref "OC1")
      (value "1200980560**OPTOCOUPLER SMD PS2561DL2-1Y-V-F3-A/L  CTR: 200˜400")
      (footprint "eagle-import:PS2561DL2-1_OPTO1")
      (libsource (lib "eagle-import") (part "PS2561DL2-1_OPTO1"))
    )
    (comp (ref "OC2")
      (value "1200980560**OPTOCOUPLER SMD PS2561DL2-1Y-V-F3-A/L  CTR: 200˜400")
      (footprint "eagle-import:PS2561DL2-1_OPTO1")
      (libsource (lib "eagle-import") (part "PS2561DL2-1_OPTO1"))
    )
    (comp (ref "PCB1")
      (value "0369-5034**PCB [ARGE?] SDA381V2CF416M3HFS2(123x113.2)")
      (footprint "eagle-import:PCB")
      (libsource (lib "eagle-import") (part "PCB"))
    )
    (comp (ref "PROG1")
      (value "NC**TAKILMAYACAK (Not Fitted)")
      (footprint "eagle-import:PROG_6PIN")
      (libsource (lib "eagle-import") (part "PROG_6PIN"))
    )
    (comp (ref "PROG2")
      (value "NC**TAKILMAYACAK (Not Fitted)")
      (footprint "eagle-import:PROG_6PIN")
      (libsource (lib "eagle-import") (part "PROG_6PIN"))
    )
    (comp (ref "Q1")
      (value "0109-4091**Mosfet N-Ch 800V 9A 0.16R TO-220FP Vishay SIHA24N80AE-GE3 [ARGE?]")
      (footprint "eagle-import:TO220BV")
      (libsource (lib "eagle-import") (part "STP5NA50"))
    )
    (comp (ref "Q2")
      (value "0109-4112**Mosfet N-Ch 27.4A 150V Rds:19mR TO-220F Fairchild FDPF190N15A")
      (footprint "eagle-import:TO220BV")
      (libsource (lib "eagle-import") (part "STP5NA50"))
    )
    (comp (ref "Q3")
      (value "1149-0006**HC49S SMD KRISTAL 8MHZ -40+85 20PF 50PPM FAT Y3MM")
      (footprint "eagle-import:HC49UP")
      (libsource (lib "eagle-import") (part "CRYSTALHC49UP"))
    )
    (comp (ref "R1")
      (value "0169-2013**Varistor 20mm 300V")
      (footprint "eagle-import:S20K40")
      (libsource (lib "eagle-import") (part "S20K40"))
    )
    (comp (ref "R2")
      (value "1200970587**RES 1206 470K %5 1/4W")
      (footprint "eagle-import:R1206_ENKO")
      (libsource (lib "eagle-import") (part "R-EU_R1206E"))
    )
    (comp (ref "R3")
      (value "1200970587**RES 1206 470K %5 1/4W")
      (footprint "eagle-import:R1206_ENKO")
      (libsource (lib "eagle-import") (part "R-EU_R1206E"))
    )
    (comp (ref "R4")
      (value "1200970587**RES 1206 470K %5 1/4W")
      (footprint "eagle-import:R1206_ENKO")
      (libsource (lib "eagle-import") (part "R-EU_R1206E"))
    )
    (comp (ref "R5")
      (value "1200970687**RES 0603 56K %1 1/10W")
      (footprint "eagle-import:R0603_ENKO")
      (libsource (lib "eagle-import") (part "R-EU_R0603E"))
    )
    (comp (ref "R6")
      (value "1200970583**RES 0603 1K %1 1/10W")
      (footprint "eagle-import:R0603_ENKO")
      (libsource (lib "eagle-import") (part "R-EU_R0603E"))
    )
    (comp (ref "R7")
      (value "1029-4050**RES 1206 6K8 %1")
      (footprint "eagle-import:R1206_ENKO")
      (libsource (lib "eagle-import") (part "R-EU_R1206E"))
    )
    (comp (ref "R8")
      (value "1029-4050**RES 1206 6K8 %1")
      (footprint "eagle-import:R1206_ENKO")
      (libsource (lib "eagle-import") (part "R-EU_R1206E"))
    )
    (comp (ref "R9")
      (value "1200970179**RES 1206 330K %5 1/4W")
      (footprint "eagle-import:R1206_ENKO")
      (libsource (lib "eagle-import") (part "R-EU_R1206E"))
    )
    (comp (ref "R10")
      (value "1200970179**RES 1206 330K %5 1/4W")
      (footprint "eagle-import:R1206_ENKO")
      (libsource (lib "eagle-import") (part "R-EU_R1206E"))
    )
    (comp (ref "R11")
      (value "1200970154**RES 1206 2K2 %5 1/4W")
      (footprint "eagle-import:R1206_ENKO")
      (libsource (lib "eagle-import") (part "R-EU_R1206E"))
    )
    (comp (ref "R12")
      (value "1200970154**RES 1206 2K2 %5 1/4W")
      (footprint "eagle-import:R1206_ENKO")
      (libsource (lib "eagle-import") (part "R-EU_R1206E"))
    )
    (comp (ref "R13")
      (value "1200970601**RES 1206 10R %5 1/4W")
      (footprint "eagle-import:R1206_ENKO")
      (libsource (lib "eagle-import") (part "R-EU_R1206E"))
    )
    (comp (ref "R14")
      (value "1200970118**RES 0805 100R %5 1/8W")
      (footprint "eagle-import:R0805_ENKO")
      (libsource (lib "eagle-import") (part "R-EU_R0805E"))
    )
    (comp (ref "R15")
      (value "1029-3008**RES 0805 22R %5")
      (footprint "eagle-import:R0805_ENKO")
      (libsource (lib "eagle-import") (part "R-EU_R0805E"))
    )
    (comp (ref "R16")
      (value "1319-4060**Ferrite Bead SMD 0805 2kOhm@100MHz 300mA LAIRD HZ0805C202R-10")
      (footprint "eagle-import:R0805_ENKO")
      (libsource (lib "eagle-import") (part "R-EU_R0805E"))
    )
    (comp (ref "R17")
      (value "1029-3146**RES 1206 7R68 %1")
      (footprint "eagle-import:R1206_ENKO")
      (libsource (lib "eagle-import") (part "R-EU_R1206E"))
    )
    (comp (ref "R18")
      (value "1029-3146**RES 1206 7R68 %1")
      (footprint "eagle-import:R1206_ENKO")
      (libsource (lib "eagle-import") (part "R-EU_R1206E"))
    )
    (comp (ref "R19")
      (value "NC**TAKILMAYACAK (Not Fitted)")
      (footprint "eagle-import:R1206_ENKO")
      (libsource (lib "eagle-import") (part "R-EU_R1206E"))
    )
    (comp (ref "R20")
      (value "1319-4060**Ferrite Bead SMD 0805 2kOhm@100MHz 300mA LAIRD HZ0805C202R-10")
      (footprint "eagle-import:R0805_ENKO")
      (libsource (lib "eagle-import") (part "R-EU_R0805E"))
    )
    (comp (ref "R21")
      (value "1200970568**RES 0603 47K %5 1/10W")
      (footprint "eagle-import:R0603_ENKO")
      (libsource (lib "eagle-import") (part "R-EU_R0603E"))
    )
    (comp (ref "R22")
      (value "1319-4060**Ferrite Bead SMD 0805 2kOhm@100MHz 300mA LAIRD HZ0805C202R-10")
      (footprint "eagle-import:R0805_ENKO")
      (libsource (lib "eagle-import") (part "R-EU_R0805E"))
    )
    (comp (ref "R23")
      (value "1029-3146**RES 1206 7R68 %1")
      (footprint "eagle-import:R1206_ENKO")
      (libsource (lib "eagle-import") (part "R-EU_R1206E"))
    )
    (comp (ref "R24")
      (value "1029-3146**RES 1206 7R68 %1")
      (footprint "eagle-import:R1206_ENKO")
      (libsource (lib "eagle-import") (part "R-EU_R1206E"))
    )
    (comp (ref "R25")
      (value "1200970228**RES 1206 47R %5 1/4W")
      (footprint "eagle-import:R1206_ENKO")
      (libsource (lib "eagle-import") (part "R-EU_R1206E"))
    )
    (comp (ref "R26")
      (value "1200970228**RES 1206 47R %5 1/4W")
      (footprint "eagle-import:R1206_ENKO")
      (libsource (lib "eagle-import") (part "R-EU_R1206E"))
    )
    (comp (ref "R27")
      (value "1029-6109**RES 2512 33R %5 1W")
      (footprint "eagle-import:R2512")
      (libsource (lib "eagle-import") (part "R-EU_R2512"))
    )
    (comp (ref "R30")
      (value "1029-6109**RES 2512 33R %5 1W")
      (footprint "eagle-import:R2512")
      (libsource (lib "eagle-import") (part "R-EU_R2512"))
    )
    (comp (ref "R31")
      (value "1029-6109**RES 2512 33R %5 1W")
      (footprint "eagle-import:R2512")
      (libsource (lib "eagle-import") (part "R-EU_R2512"))
    )
    (comp (ref "R33")
      (value "1029-6109**RES 2512 33R %5 1W")
      (footprint "eagle-import:R2512")
      (libsource (lib "eagle-import") (part "R-EU_R2512"))
    )
    (comp (ref "R34")
      (value "1029-6109**RES 2512 33R %5 1W")
      (footprint "eagle-import:R2512")
      (libsource (lib "eagle-import") (part "R-EU_R2512"))
    )
    (comp (ref "R35")
      (value "1029-3116**RES 0805 10R %5")
      (footprint "eagle-import:R0805_ENKO")
      (libsource (lib "eagle-import") (part "R-EU_R0805E"))
    )
    (comp (ref "R36")
      (value "1200970117**RES 1206 0R %5")
      (footprint "eagle-import:R1206_ENKO")
      (libsource (lib "eagle-import") (part "R-EU_R1206E"))
    )
    (comp (ref "R38")
      (value "1200970568**RES 0603 47K %5 1/10W")
      (footprint "eagle-import:R0603_ENKO")
      (libsource (lib "eagle-import") (part "R-EU_R0603E"))
    )
    (comp (ref "R39")
      (value "1200970228**RES 1206 47R %5 1/4W")
      (footprint "eagle-import:R1206_ENKO")
      (libsource (lib "eagle-import") (part "R-EU_R1206E"))
    )
    (comp (ref "R40")
      (value "1200970228**RES 1206 47R %5 1/4W")
      (footprint "eagle-import:R1206_ENKO")
      (libsource (lib "eagle-import") (part "R-EU_R1206E"))
    )
    (comp (ref "R41")
      (value "1200970228**RES 1206 47R %5 1/4W")
      (footprint "eagle-import:R1206_ENKO")
      (libsource (lib "eagle-import") (part "R-EU_R1206E"))
    )
    (comp (ref "R42")
      (value "1200970228**RES 1206 47R %5 1/4W")
      (footprint "eagle-import:R1206_ENKO")
      (libsource (lib "eagle-import") (part "R-EU_R1206E"))
    )
    (comp (ref "R43")
      (value "1200970228**RES 1206 47R %5 1/4W")
      (footprint "eagle-import:R1206_ENKO")
      (libsource (lib "eagle-import") (part "R-EU_R1206E"))
    )
    (comp (ref "R44")
      (value "1200970568**RES 0603 47K %5 1/10W")
      (footprint "eagle-import:R0603_ENKO")
      (libsource (lib "eagle-import") (part "R-EU_R0603E"))
    )
    (comp (ref "R45")
      (value "1319-4060**Ferrite Bead SMD 0805 2kOhm@100MHz 300mA LAIRD HZ0805C202R-10")
      (footprint "eagle-import:R0805_ENKO")
      (libsource (lib "eagle-import") (part "R-EU_R0805E"))
    )
    (comp (ref "R46")
      (value "1200970518**RES 0603 10K %5 1/10W")
      (footprint "eagle-import:R0603_ENKO")
      (libsource (lib "eagle-import") (part "R-EU_R0603E"))
    )
    (comp (ref "R47")
      (value "1200971020**RES 0603 10K %1 1/10W")
      (footprint "eagle-import:R0603_ENKO")
      (libsource (lib "eagle-import") (part "R-EU_R0603E"))
    )
    (comp (ref "R48")
      (value "1200970516**RES 0603 22K %5 1/10W")
      (footprint "eagle-import:R0603_ENKO")
      (libsource (lib "eagle-import") (part "R-EU_R0603E"))
    )
    (comp (ref "R49")
      (value "1029-2005**RES 0603 220R %1")
      (footprint "eagle-import:R0603_ENKO")
      (libsource (lib "eagle-import") (part "R-EU_R0603E"))
    )
    (comp (ref "R50")
      (value "1200970803**RES 0603 100K %1 1/10W")
      (footprint "eagle-import:R0603_ENKO")
      (libsource (lib "eagle-import") (part "R-EU_R0603E"))
    )
    (comp (ref "R51")
      (value "1200971020**RES 0603 10K %1 1/10W")
      (footprint "eagle-import:R0603_ENKO")
      (libsource (lib "eagle-import") (part "R-EU_R0603E"))
    )
    (comp (ref "R52")
      (value "1029-2005**RES 0603 220R %1")
      (footprint "eagle-import:R0603_ENKO")
      (libsource (lib "eagle-import") (part "R-EU_R0603E"))
    )
    (comp (ref "R53")
      (value "1029-2005**RES 0603 220R %1")
      (footprint "eagle-import:R0603_ENKO")
      (libsource (lib "eagle-import") (part "R-EU_R0603E"))
    )
    (comp (ref "R54")
      (value "1200971020**RES 0603 10K %1 1/10W")
      (footprint "eagle-import:R0603_ENKO")
      (libsource (lib "eagle-import") (part "R-EU_R0603E"))
    )
    (comp (ref "R55")
      (value "1029-2233**RES 0603 2K2 %1")
      (footprint "eagle-import:R0603_ENKO")
      (libsource (lib "eagle-import") (part "rcl_334_R-EU_R0603E"))
    )
    (comp (ref "R56")
      (value "1200970522**RES 0603 1K %5 1/10W")
      (footprint "eagle-import:R0603_ENKO")
      (libsource (lib "eagle-import") (part "R-EU_R0603E"))
    )
    (comp (ref "R57")
      (value "1200970803**RES 0603 100K %1 1/10W")
      (footprint "eagle-import:R0603_ENKO")
      (libsource (lib "eagle-import") (part "R-EU_R0603E"))
    )
    (comp (ref "R58")
      (value "1200970770**RES 0603 4K3 %1 1/10W")
      (footprint "eagle-import:R0603_ENKO")
      (libsource (lib "eagle-import") (part "R-EU_R0603E"))
    )
    (comp (ref "R59")
      (value "1200970803**RES 0603 100K %1 1/10W")
      (footprint "eagle-import:R0603_ENKO")
      (libsource (lib "eagle-import") (part "R-EU_R0603E"))
    )
    (comp (ref "R60")
      (value "1200970583**RES 0603 1K %1 1/10W")
      (footprint "eagle-import:R0603_ENKO")
      (libsource (lib "eagle-import") (part "R-EU_R0603E"))
    )
    (comp (ref "R61")
      (value "1200970583**RES 0603 1K %1 1/10W")
      (footprint "eagle-import:R0603_ENKO")
      (libsource (lib "eagle-import") (part "R-EU_R0603E"))
    )
    (comp (ref "R62")
      (value "1200970706**RES 0603 1K8 %5 1/10W")
      (footprint "eagle-import:R0603_ENKO")
      (libsource (lib "eagle-import") (part "R-EU_R0603E"))
    )
    (comp (ref "R63")
      (value "1029-2003**RES 0603 10R %1")
      (footprint "eagle-import:R0603_ENKO")
      (libsource (lib "eagle-import") (part "R-EU_R0603E"))
    )
    (comp (ref "R64")
      (value "1029-2006**RES 0603 47R %1")
      (footprint "eagle-import:R0603_ENKO")
      (libsource (lib "eagle-import") (part "R-EU_R0603E"))
    )
    (comp (ref "R65")
      (value "1029-6021**RES 2512 0R003 %1 2W")
      (footprint "eagle-import:R2512")
      (libsource (lib "eagle-import") (part "R-EU_R2512"))
    )
    (comp (ref "R66")
      (value "1200970927**RES 0603 100R %1 1/10W")
      (footprint "eagle-import:R0603_ENKO")
      (libsource (lib "eagle-import") (part "R-EU_R0603E"))
    )
    (comp (ref "R67")
      (value "1200970522**RES 0603 1K %5 1/10W")
      (footprint "eagle-import:R0603_ENKO")
      (libsource (lib "eagle-import") (part "R-EU_R0603E"))
    )
    (comp (ref "R68")
      (value "1200970522**RES 0603 1K %5 1/10W")
      (footprint "eagle-import:R0603_ENKO")
      (libsource (lib "eagle-import") (part "R-EU_R0603E"))
    )
    (comp (ref "R69")
      (value "1029-3116**RES 0805 10R %5")
      (footprint "eagle-import:R0805_ENKO")
      (libsource (lib "eagle-import") (part "R-EU_R0805E"))
    )
    (comp (ref "R70")
      (value "1200971020**RES 0603 10K %1 1/10W")
      (footprint "eagle-import:R0603_ENKO")
      (libsource (lib "eagle-import") (part "rcl_334_R-EU_R0603E"))
    )
    (comp (ref "R71")
      (value "1029-2234**RES 0603 4K7 %1")
      (footprint "eagle-import:R0603_ENKO")
      (libsource (lib "eagle-import") (part "R-EU_R0603E"))
    )
    (comp (ref "R72")
      (value "1200970583**RES 0603 1K %1 1/10W")
      (footprint "eagle-import:R0603_ENKO")
      (libsource (lib "eagle-import") (part "R-EU_R0603E"))
    )
    (comp (ref "R73")
      (value "1169-1001**TSM2A103F3951RZ THINKING 0805 10K NTC 125C")
      (footprint "eagle-import:R0805_ENKO")
      (libsource (lib "eagle-import") (part "R-EU_R0805E"))
    )
    (comp (ref "R74")
      (value "1200970156**RES 1206 22K %5 1/4W")
      (footprint "eagle-import:R1206_ENKO")
      (libsource (lib "eagle-import") (part "R-EU_R1206E"))
    )
    (comp (ref "R75")
      (value "1200970583**RES 0603 1K %1 1/10W")
      (footprint "eagle-import:R0603_ENKO")
      (libsource (lib "eagle-import") (part "R-EU_R0603E"))
    )
    (comp (ref "R76")
      (value "1200970803**RES 0603 100K %1 1/10W")
      (footprint "eagle-import:R0603_ENKO")
      (libsource (lib "eagle-import") (part "rcl_334_R-EU_R0603E"))
    )
    (comp (ref "R77")
      (value "1029-6089**RES 0603 6K8 %5")
      (footprint "eagle-import:R0603_ENKO")
      (libsource (lib "eagle-import") (part "R-EU_R0603E"))
    )
    (comp (ref "R78")
      (value "1029-2203**RES 0603 12K %1")
      (footprint "eagle-import:R0603_ENKO")
      (libsource (lib "eagle-import") (part "R-EU_R0603E"))
    )
    (comp (ref "R79")
      (value "1029-2341**RES 0603 5K6 %1")
      (footprint "eagle-import:R0603_ENKO")
      (libsource (lib "eagle-import") (part "rcl_334_R-EU_R0603E"))
    )
    (comp (ref "R80")
      (value "1029-2234**RES 0603 4K7 %1")
      (footprint "eagle-import:R0603_ENKO")
      (libsource (lib "eagle-import") (part "rcl_334_R-EU_R0603E"))
    )
    (comp (ref "R81")
      (value "1200970583**RES 0603 1K %1 1/10W")
      (footprint "eagle-import:R0603_ENKO")
      (libsource (lib "eagle-import") (part "R-EU_R0603E"))
    )
    (comp (ref "R82")
      (value "1200971020**RES 0603 10K %1 1/10W")
      (footprint "eagle-import:R0603_ENKO")
      (libsource (lib "eagle-import") (part "R-EU_R0603E"))
    )
    (comp (ref "R83")
      (value "1200970522**RES 0603 1K %5 1/10W")
      (footprint "eagle-import:R0603_ENKO")
      (libsource (lib "eagle-import") (part "R-EU_R0603E"))
    )
    (comp (ref "R84")
      (value "1200970522**RES 0603 1K %5 1/10W")
      (footprint "eagle-import:R0603_ENKO")
      (libsource (lib "eagle-import") (part "R-EU_R0603E"))
    )
    (comp (ref "R85")
      (value "1169-1006**FUSE SMD 1206 PTC RESETTABLE 16V IHOLD=0.75A IMAX=100A")
      (footprint "eagle-import:R1206_ENKO")
      (libsource (lib "eagle-import") (part "R-EU_R1206E"))
    )
    (comp (ref "R86")
      (value "1200970522**RES 0603 1K %5 1/10W")
      (footprint "eagle-import:R0603_ENKO")
      (libsource (lib "eagle-import") (part "R-EU_R0603E"))
    )
    (comp (ref "R87")
      (value "1200970518**RES 0603 10K %5 1/10W")
      (footprint "eagle-import:R0603_ENKO")
      (libsource (lib "eagle-import") (part "R-EU_R0603E"))
    )
    (comp (ref "R88")
      (value "1029-2234**RES 0603 4K7 %1")
      (footprint "eagle-import:R0603_ENKO")
      (libsource (lib "eagle-import") (part "R-EU_R0603E"))
    )
    (comp (ref "R89")
      (value "1200970583**RES 0603 1K %1 1/10W")
      (footprint "eagle-import:R0603_ENKO")
      (libsource (lib "eagle-import") (part "R-EU_R0603E"))
    )
    (comp (ref "R90")
      (value "1029-2231**RES 0603 1K8 %1")
      (footprint "eagle-import:R0603_ENKO")
      (libsource (lib "eagle-import") (part "R-EU_R0603E"))
    )
    (comp (ref "R91")
      (value "1200970518**RES 0603 10K %5 1/10W")
      (footprint "eagle-import:R0603_ENKO")
      (libsource (lib "eagle-import") (part "R-EU_R0603E"))
    )
    (comp (ref "R92")
      (value "1200970568**RES 0603 47K %5 1/10W")
      (footprint "eagle-import:R0603_ENKO")
      (libsource (lib "eagle-import") (part "R-EU_R0603E"))
    )
    (comp (ref "R93")
      (value "1409-0025**RES 0603 470R %5 1/16W")
      (footprint "eagle-import:R0603_ENKO")
      (libsource (lib "eagle-import") (part "R-EU_R0603E"))
    )
    (comp (ref "R94")
      (value "1029-6086**RES 0603 22R %1")
      (footprint "eagle-import:R0603_ENKO")
      (libsource (lib "eagle-import") (part "R-EU_R0603E"))
    )
    (comp (ref "R95")
      (value "1200970522**RES 0603 1K %5 1/10W")
      (footprint "eagle-import:R0603_ENKO")
      (libsource (lib "eagle-import") (part "R-EU_R0603E"))
    )
    (comp (ref "R96")
      (value "1029-6086**RES 0603 22R %1")
      (footprint "eagle-import:R0603_ENKO")
      (libsource (lib "eagle-import") (part "R-EU_R0603E"))
    )
    (comp (ref "R97")
      (value "1029-6086**RES 0603 22R %1")
      (footprint "eagle-import:R0603_ENKO")
      (libsource (lib "eagle-import") (part "R-EU_R0603E"))
    )
    (comp (ref "R98")
      (value "1029-2234**RES 0603 4K7 %1")
      (footprint "eagle-import:R0603_ENKO")
      (libsource (lib "eagle-import") (part "R-EU_R0603E"))
    )
    (comp (ref "R99")
      (value "1200970518**RES 0603 10K %5 1/10W")
      (footprint "eagle-import:R0603_ENKO")
      (libsource (lib "eagle-import") (part "R-EU_R0603E"))
    )
    (comp (ref "R100")
      (value "1200970852**RES 0603 1K5 %5 1/10W ( <-1029-3501 )")
      (footprint "eagle-import:R0603_ENKO")
      (libsource (lib "eagle-import") (part "R-EU_R0603E"))
    )
    (comp (ref "R101")
      (value "1200970684**RES 0603 47K %1 1/10W")
      (footprint "eagle-import:R0603_ENKO")
      (libsource (lib "eagle-import") (part "R-EU_R0603E"))
    )
    (comp (ref "R102")
      (value "1200970583**RES 0603 1K %1 1/10W")
      (footprint "eagle-import:R0603_ENKO")
      (libsource (lib "eagle-import") (part "R-EU_R0603E"))
    )
    (comp (ref "R103")
      (value "1200970522**RES 0603 1K %5 1/10W")
      (footprint "eagle-import:R0603_ENKO")
      (libsource (lib "eagle-import") (part "R-EU_R0603E"))
    )
    (comp (ref "R104")
      (value "1200970522**RES 0603 1K %5 1/10W")
      (footprint "eagle-import:R0603_ENKO")
      (libsource (lib "eagle-import") (part "R-EU_R0603E"))
    )
    (comp (ref "R105")
      (value "1029-2229**RES 0603 120K %1")
      (footprint "eagle-import:R0603_ENKO")
      (libsource (lib "eagle-import") (part "R-EU_R0603E"))
    )
    (comp (ref "R106")
      (value "1029-2219**RES 0603 30K %1")
      (footprint "eagle-import:R0603_ENKO")
      (libsource (lib "eagle-import") (part "R-EU_R0603E"))
    )
    (comp (ref "R107")
      (value "1200970515**RES 0603 100K %5 1/10W")
      (footprint "eagle-import:R0603_ENKO")
      (libsource (lib "eagle-import") (part "R-EU_R0603E"))
    )
    (comp (ref "R108")
      (value "1200970730**RES 0603 560R %1 1/10W")
      (footprint "eagle-import:R0603_ENKO")
      (libsource (lib "eagle-import") (part "R-EU_R0603E"))
    )
    (comp (ref "R109")
      (value "1200970518**RES 0603 10K %5 1/10W")
      (footprint "eagle-import:R0603_ENKO")
      (libsource (lib "eagle-import") (part "R-EU_R0603E"))
    )
    (comp (ref "R110")
      (value "1200970516**RES 0603 22K %5 1/10W")
      (footprint "eagle-import:R0603_ENKO")
      (libsource (lib "eagle-import") (part "R-EU_R0603E"))
    )
    (comp (ref "R112")
      (value "1200970154**RES 1206 2K2 %5 1/4W")
      (footprint "eagle-import:R1206_ENKO")
      (libsource (lib "eagle-import") (part "R-EU_R1206E"))
    )
    (comp (ref "R113")
      (value "1200970121**RES 0805 1K %5 1/8W")
      (footprint "eagle-import:R0805_ENKO")
      (libsource (lib "eagle-import") (part "R-EU_R0805E"))
    )
    (comp (ref "R114")
      (value "1200970518**RES 0603 10K %5 1/10W")
      (footprint "eagle-import:R0603_ENKO")
      (libsource (lib "eagle-import") (part "R-EU_R0603E"))
    )
    (comp (ref "R115")
      (value "1200970853**RES 1206 39K %1 1/4W")
      (footprint "eagle-import:R1206_ENKO")
      (libsource (lib "eagle-import") (part "R-EU_R1206E"))
    )
    (comp (ref "R116")
      (value "1200970585**RES 0603 1M %5 1/10W")
      (footprint "eagle-import:R0603_ENKO")
      (libsource (lib "eagle-import") (part "R-EU_R0603E"))
    )
    (comp (ref "R117")
      (value "1029-6015**RES 1206 56K %5")
      (footprint "eagle-import:R1206_ENKO")
      (libsource (lib "eagle-import") (part "R-EU_R1206E"))
    )
    (comp (ref "R118")
      (value "1029-6106**RES 2512 270mR %1 2W [ARGE?]")
      (footprint "eagle-import:R2512")
      (libsource (lib "eagle-import") (part "R-EU_R2512"))
    )
    (comp (ref "R119")
      (value "1029-6106**RES 2512 270mR %1 2W [ARGE?]")
      (footprint "eagle-import:R2512")
      (libsource (lib "eagle-import") (part "R-EU_R2512"))
    )
    (comp (ref "R133")
      (value "1200970626**RES 0603 82K %1 1/10W")
      (footprint "eagle-import:R0603_ENKO")
      (libsource (lib "eagle-import") (part "R-EU_R0603E"))
    )
    (comp (ref "R134")
      (value "1029-2234**RES 0603 4K7 %1")
      (footprint "eagle-import:R0603_ENKO")
      (libsource (lib "eagle-import") (part "R-EU_R0603E"))
    )
    (comp (ref "R135")
      (value "1200970940**RES 0603 6K8 %1 1/10W")
      (footprint "eagle-import:R0603_ENKO")
      (libsource (lib "eagle-import") (part "R-EU_R0603E"))
    )
    (comp (ref "R193")
      (value "1200970934**RES 0603 470K %1 1/10W")
      (footprint "eagle-import:R0603_ENKO")
      (libsource (lib "eagle-import") (part "R-EU_R0603E"))
    )
    (comp (ref "R194")
      (value "1200970528**RES 0603 0R %5 1/10W")
      (footprint "eagle-import:R0603_ENKO")
      (libsource (lib "eagle-import") (part "R-EU_R0603E"))
    )
    (comp (ref "RL1")
      (value "1200930051**RELAY SPST 12V 5A 7x15x20.3mm")
      (footprint "eagle-import:ALD1_AND_ALJ_RELAY")
      (libsource (lib "eagle-import") (part "ALD1_AND_ALJ_RELAY"))
    )
    (comp (ref "STENCIL")
      (value "041-7516**SDA381V2 için Çerçeveli Elek (Stencil) (600x600)")
      (footprint "eagle-import:PCB")
      (libsource (lib "eagle-import") (part "PCB"))
    )
    (comp (ref "T1")
      (value "1109-1016**Transistor NPN 3A 100V 15W Hfemin:10 DPAK Diodes MJD31C-13")
      (footprint "eagle-import:DPAK")
      (libsource (lib "eagle-import") (part "MJD31C"))
    )
    (comp (ref "T1_X")
      (value "1200980090**TRANS SMD NPN BC847B SOT-23")
      (footprint "eagle-import:SOT23")
      (libsource (lib "eagle-import") (part "BC848SMDALT1"))
    )
    (comp (ref "T3")
      (value "1200980091**TRANS SMD PNP BC857B SOT-23")
      (footprint "eagle-import:SOT23-BEC")
      (libsource (lib "eagle-import") (part "-PNP-SOT23-BECBC856B"))
    )
    (comp (ref "T4")
      (value "1200980090**TRANS SMD NPN BC847B SOT-23")
      (footprint "eagle-import:SOT23")
      (libsource (lib "eagle-import") (part "BC848SMDALT1"))
    )
    (comp (ref "T5")
      (value "1200980090**TRANS SMD NPN BC847B SOT-23")
      (footprint "eagle-import:SOT23")
      (libsource (lib "eagle-import") (part "BC848SMDALT1"))
    )
    (comp (ref "T6")
      (value "1200980090**TRANS SMD NPN BC847B SOT-23")
      (footprint "eagle-import:SOT23")
      (libsource (lib "eagle-import") (part "BC848SMDALT1"))
    )
    (comp (ref "T7")
      (value "1200980090**TRANS SMD NPN BC847B SOT-23")
      (footprint "eagle-import:SOT23")
      (libsource (lib "eagle-import") (part "BC848SMDALT1"))
    )
    (comp (ref "T9")
      (value "1200980090**TRANS SMD NPN BC847B SOT-23")
      (footprint "eagle-import:SOT23")
      (libsource (lib "eagle-import") (part "BC848SMDALT1"))
    )
    (comp (ref "T10")
      (value "1049-1012**MMBTA56 PNP 80V 500mA 330mW hfe(min):100 SOT23")
      (footprint "eagle-import:SOT23-BEC")
      (libsource (lib "eagle-import") (part "-PNP-SOT23-BECBC856B"))
    )
    (comp (ref "TP1")
      (value "PTR1TP20R")
      (footprint "eagle-import:TP20R")
      (libsource (lib "eagle-import") (part "PTR1TP20R"))
    )
    (comp (ref "TP4")
      (value "PTR1TP20R")
      (footprint "eagle-import:TP20R")
      (libsource (lib "eagle-import") (part "PTR1TP20R"))
    )
    (comp (ref "TRF1")
      (value "0319-7452**SMPS TRAFO 150W E42/21/15 300uH DBC2 [ARGE?]")
      (footprint "eagle-import:DEIF_TRF")
      (libsource (lib "eagle-import") (part "DEIF_TRF"))
    )
    (comp (ref "TVS1")
      (value "1119-3061**5V 130W TVS Diode SOD-323")
      (footprint "eagle-import:SOD323")
      (libsource (lib "eagle-import") (part "TVS-BD-SOD323"))
    )
    (comp (ref "U1")
      (value "1039-2220**STM32F072C8T6 64K Flash USB, CAN")
      (footprint "eagle-import:STM32F072CXXX_LQFP48")
      (libsource (lib "eagle-import") (part "STM32F072CXXX_LQFP48"))
    )
    (comp (ref "U2")
      (value "1039-2392**LMR16006XDDCR 0.6A, 0.7MHz Step-Down Converter in a TSOT-6L, Input 4V to 60V")
      (footprint "eagle-import:AOZ1282CI-1")
      (libsource (lib "eagle-import") (part "AOZ1282CI-1"))
    )
    (comp (ref "X1")
      (value "0289-1462**GMSTBA 2.5/ 3-G-7.62 (Phoenix 1766246)")
      (footprint "eagle-import:GMSTBA3")
      (fields (field (name "MF") "FARNELL") (field (name "MPN") "1757255"))
      (libsource (lib "eagle-import") (part "GMSTBA3"))
    )
    (comp (ref "X2")
      (value "0309-1064**USB Type-B Mini Connector Horizantal")
      (footprint "eagle-import:USB_B(YATIK)")
      (libsource (lib "eagle-import") (part "USB_B(YATIK)"))
    )
    (comp (ref "X3")
      (value "0289-1460**MSTBA 2.5/ 4-G-5.08 (Phoenix 1757268)")
      (footprint "eagle-import:MSTBA4")
      (fields (field (name "MF") "FARNELL") (field (name "MPN") "1757268"))
      (libsource (lib "eagle-import") (part "MSTBA4"))
    )
    (comp (ref "X4")
      (value "0289-1464**MSTBA 2.5/ 3-G-5.08 (Phoenix 1757255)")
      (footprint "eagle-import:MSTBA3")
      (fields (field (name "MF") "FARNELL") (field (name "MPN") "1757255"))
      (libsource (lib "eagle-import") (part "MSTBA3"))
    )
    (comp (ref "XK1")
      (value "0289-1463**GMVSTBR 2.5/ 3-ST-7.62 (Phoenix 1832536)")
      (footprint "eagle-import:SOKET")
      (libsource (lib "eagle-import") (part "SOKET"))
    )
    (comp (ref "XK3")
      (value "0289-1461**MVSTBR 2.5/ 4-ST-5.08 (Phoenix 1792265)")
      (footprint "eagle-import:SOKET")
      (libsource (lib "eagle-import") (part "SOKET"))
    )
    (comp (ref "XK4")
      (value "0289-1465**MVSTBR 2.5/ 3-ST-5.08 (Phoenix 1792252)")
      (footprint "eagle-import:SOKET")
      (libsource (lib "eagle-import") (part "SOKET"))
    )
    (comp (ref "Z1")
      (value "1129-1195**ZENER SOT23 18V 400mW %5 BZX84C18V")
      (footprint "eagle-import:SOT23")
      (libsource (lib "eagle-import") (part "ZENER-DIODESOT23"))
    )
    (comp (ref "Z2")
      (value "NC**TAKILMAYACAK (Not Fitted)")
      (footprint "eagle-import:SOT23")
      (libsource (lib "eagle-import") (part "ZENER-DIODESOT23"))
    )
    (comp (ref "Z4")
      (value "1129-1162**ZENER SOT23 3V9 300mW BZX84C3V9")
      (footprint "eagle-import:SOT23")
      (libsource (lib "eagle-import") (part "ZENER-DIODESOT23"))
    )
    (comp (ref "Z5")
      (value "1129-1145**ZENER SOT23 0.3W 15V BZX84C15")
      (footprint "eagle-import:SOT23")
      (libsource (lib "eagle-import") (part "ZENER-DIODESOT23"))
    )
    (comp (ref "Z6")
      (value "1129-1145**ZENER SOT23 0.3W 15V BZX84C15")
      (footprint "eagle-import:SOT23")
      (libsource (lib "eagle-import") (part "ZENER-DIODESOT23"))
    )
    (comp (ref "Z7")
      (value "1129-1151**ZENER SOT23 12V 225mW BZX84C12")
      (footprint "eagle-import:SOT23")
      (libsource (lib "eagle-import") (part "ZENER-DIODESOT23"))
    )
    (comp (ref "Z8")
      (value "1129-1140**ZENER SOT23 5V1 0.4W BZX84C5V1")
      (footprint "eagle-import:SOT23")
      (libsource (lib "eagle-import") (part "ZENER-DIODESOT23"))
    )
  )
  (nets
    (net (code "1") (name "+3V3") (class "Default")
      (node (ref "C38") (pin "1") (pinfunction "1_1") (pintype "passive"))
      (node (ref "C39") (pin "1") (pinfunction "1_1") (pintype "passive"))
      (node (ref "C45") (pin "1") (pinfunction "1_1") (pintype "passive"))
      (node (ref "C48") (pin "1") (pinfunction "1_1") (pintype "passive"))
      (node (ref "C49") (pin "1") (pinfunction "1_1") (pintype "passive"))
      (node (ref "C51") (pin "1") (pinfunction "1_1") (pintype "passive"))
      (node (ref "C54") (pin "1") (pinfunction "1_1") (pintype "passive"))
      (node (ref "C55") (pin "1") (pinfunction "1_1") (pintype "passive"))
      (node (ref "C57") (pin "1") (pinfunction "1_1") (pintype "passive"))
      (node (ref "D13") (pin "2") (pinfunction "C_2") (pintype "passive"))
      (node (ref "IC4") (pin "3") (pinfunction "OUT_3") (pintype "passive"))
      (node (ref "IC5") (pin "8") (pinfunction "V+_8") (pintype "power_in"))
      (node (ref "LED1") (pin "2") (pinfunction "2_2") (pintype "passive"))
      (node (ref "PROG1") (pin "1") (pinfunction "+3V3_1") (pintype "passive"))
      (node (ref "PROG2") (pin "1") (pinfunction "+3V3_1") (pintype "passive"))
      (node (ref "R100") (pin "2") (pinfunction "2_2") (pintype "passive"))
      (node (ref "R110") (pin "2") (pinfunction "2_2") (pintype "passive"))
      (node (ref "R45") (pin "2") (pinfunction "2_2") (pintype "passive"))
      (node (ref "R46") (pin "1") (pinfunction "1_1") (pintype "passive"))
      (node (ref "R72") (pin "2") (pinfunction "2_2") (pintype "passive"))
      (node (ref "U1") (pin "24") (pinfunction "VDD._24") (pintype "bidirectional"))
      (node (ref "U1") (pin "36") (pinfunction "VDDIO2_36") (pintype "bidirectional"))
      (node (ref "U1") (pin "48") (pinfunction "VDD_48") (pintype "bidirectional"))
    )
    (net (code "2") (name "/13.8V+") (class "Default")
      (node (ref "C18") (pin "P$1") (pinfunction "1_P$1") (pintype "passive"))
      (node (ref "C24") (pin "P$1") (pinfunction "1_P$1") (pintype "passive"))
      (node (ref "C36") (pin "1") (pinfunction "1_1") (pintype "passive"))
      (node (ref "C37") (pin "1") (pinfunction "1_1") (pintype "passive"))
      (node (ref "C40") (pin "+") (pinfunction "+_+") (pintype "passive"))
      (node (ref "C40") (pin "+1") (pinfunction "+_+1") (pintype "passive"))
      (node (ref "C42") (pin "+") (pinfunction "+_+") (pintype "passive"))
      (node (ref "C72") (pin "2") (pinfunction "2_2") (pintype "passive"))
      (node (ref "C73") (pin "1") (pinfunction "1_1") (pintype "passive"))
      (node (ref "C74") (pin "1") (pinfunction "1_1") (pintype "passive"))
      (node (ref "D7") (pin "A") (pinfunction "A_A") (pintype "passive"))
      (node (ref "L6") (pin "1") (pinfunction "1_1") (pintype "passive"))
      (node (ref "OC2") (pin "1") (pinfunction "1_1") (pintype "passive"))
      (node (ref "R117") (pin "1") (pinfunction "1_1") (pintype "passive"))
      (node (ref "R50") (pin "1") (pinfunction "1_1") (pintype "passive"))
      (node (ref "R78") (pin "2") (pinfunction "2_2") (pintype "passive"))
      (node (ref "TRF1") (pin "10") (pinfunction "13_10") (pintype "passive"))
      (node (ref "TRF1") (pin "21") (pinfunction "13_21") (pintype "passive"))
      (node (ref "TRF1") (pin "22") (pinfunction "12_22") (pintype "passive"))
      (node (ref "TRF1") (pin "29") (pinfunction "12_29") (pintype "passive"))
      (node (ref "TRF1") (pin "30") (pinfunction "13_30") (pintype "passive"))
      (node (ref "TRF1") (pin "43") (pinfunction "12_43") (pintype "passive"))
      (node (ref "TRF1") (pin "44") (pinfunction "13_44") (pintype "passive"))
      (node (ref "TRF1") (pin "9") (pinfunction "12_9") (pintype "passive"))
    )
    (net (code "3") (name "/I_FOR_REV_BAT_PROTEC") (class "Default")
      (node (ref "C50") (pin "2") (pinfunction "2_2") (pintype "passive"))
      (node (ref "IC5") (pin "3") (pinfunction "+IN_3") (pintype "input"))
      (node (ref "IC5") (pin "7") (pinfunction "OUT_7") (pintype "output"))
      (node (ref "R109") (pin "2") (pinfunction "2_2") (pintype "passive"))
      (node (ref "R71") (pin "2") (pinfunction "2_2") (pintype "passive"))
    )
    (net (code "4") (name "/N$69") (class "Default")
      (node (ref "C46") (pin "1") (pinfunction "1_1") (pintype "passive"))
      (node (ref "C71") (pin "2") (pinfunction "2_2") (pintype "passive"))
      (node (ref "IC3") (pin "6") (pinfunction "GND_6") (pintype "power_in"))
      (node (ref "IC8") (pin "S") (pinfunction "S123_S") (pintype "passive"))
      (node (ref "IC8") (pin "S1") (pinfunction "S123_S1") (pintype "passive"))
      (node (ref "IC8") (pin "S2") (pinfunction "S123_S2") (pintype "passive"))
      (node (ref "R114") (pin "2") (pinfunction "2_2") (pintype "passive"))
      (node (ref "R116") (pin "1") (pinfunction "1_1") (pintype "passive"))
      (node (ref "R65") (pin "2") (pinfunction "2_2") (pintype "passive"))
      (node (ref "R66") (pin "2") (pinfunction "2_2") (pintype "passive"))
      (node (ref "R67") (pin "2") (pinfunction "2_2") (pintype "passive"))
      (node (ref "R80") (pin "1") (pinfunction "1_1") (pintype "passive"))
      (node (ref "T7") (pin "2") (pinfunction "E_2") (pintype "passive"))
      (node (ref "T9") (pin "2") (pinfunction "E_2") (pintype "passive"))
      (node (ref "Z7") (pin "1") (pinfunction "A_1") (pintype "passive"))
      (node (ref "Z8") (pin "1") (pinfunction "A_1") (pintype "passive"))
    )
    (net (code "5") (name "/N$84") (class "Default")
      (node (ref "C21") (pin "1") (pinfunction "1_1") (pintype "passive"))
      (node (ref "IC2") (pin "6") (pinfunction "6.CS_6") (pintype "input"))
      (node (ref "Q2") (pin "D") (pinfunction "D_D") (pintype "passive"))
      (node (ref "TRF1") (pin "11") (pinfunction "14_11") (pintype "passive"))
      (node (ref "TRF1") (pin "12") (pinfunction "15_12") (pintype "passive"))
      (node (ref "TRF1") (pin "13") (pinfunction "16_13") (pintype "passive"))
      (node (ref "TRF1") (pin "19") (pinfunction "15_19") (pintype "passive"))
      (node (ref "TRF1") (pin "20") (pinfunction "14_20") (pintype "passive"))
      (node (ref "TRF1") (pin "25") (pinfunction "16_25") (pintype "passive"))
      (node (ref "TRF1") (pin "31") (pinfunction "14_31") (pintype "passive"))
      (node (ref "TRF1") (pin "32") (pinfunction "15_32") (pintype "passive"))
      (node (ref "TRF1") (pin "38") (pinfunction "16_38") (pintype "passive"))
      (node (ref "TRF1") (pin "45") (pinfunction "14_45") (pintype "passive"))
      (node (ref "TRF1") (pin "46") (pinfunction "15_46") (pintype "passive"))
      (node (ref "TRF1") (pin "47") (pinfunction "16_47") (pintype "passive"))
    )
    (net (code "6") (name "/OSC1") (class "Default")
      (node (ref "C23") (pin "1") (pinfunction "1_1") (pintype "passive"))
      (node (ref "Q3") (pin "1") (pinfunction "1_1") (pintype "passive"))
      (node (ref "U1") (pin "5") (pinfunction "PF0/OSC_IN_5") (pintype "bidirectional"))
    )
    (net (code "7") (name "/OSC2") (class "Default")
      (node (ref "C26") (pin "1") (pinfunction "1_1") (pintype "passive"))
      (node (ref "Q3") (pin "2") (pinfunction "2_2") (pintype "passive"))
      (node (ref "U1") (pin "6") (pinfunction "PF1/OSC_OUT_6") (pintype "bidirectional"))
    )
    (net (code "8") (name "/PRI_SOURCE") (class "Default")
      (node (ref "C22") (pin "P$2") (pinfunction "2_P$2") (pintype "passive"))
      (node (ref "C25") (pin "2") (pinfunction "2_2") (pintype "passive"))
      (node (ref "H1") (pin "1") (pinfunction "P$1_1") (pintype "bidirectional"))
      (node (ref "H1") (pin "2") (pinfunction "P$1_2") (pintype "bidirectional"))
      (node (ref "H1") (pin "3") (pinfunction "P$2_3") (pintype "bidirectional"))
      (node (ref "H1") (pin "4") (pinfunction "P$2_4") (pintype "bidirectional"))
      (node (ref "Q1") (pin "S") (pinfunction "S_S") (pintype "passive"))
      (node (ref "R118") (pin "2") (pinfunction "2_2") (pintype "passive"))
      (node (ref "R119") (pin "2") (pinfunction "2_2") (pintype "passive"))
      (node (ref "R21") (pin "1") (pinfunction "1_1") (pintype "passive"))
      (node (ref "R27") (pin "1") (pinfunction "1_1") (pintype "passive"))
      (node (ref "R6") (pin "2") (pinfunction "2_2") (pintype "passive"))
    )
    (net (code "9") (name "/REG_INP") (class "Default")
      (node (ref "C47") (pin "1") (pinfunction "1_1") (pintype "passive"))
      (node (ref "D8") (pin "C") (pinfunction "C_C") (pintype "passive"))
      (node (ref "D9") (pin "3") (pinfunction "C_3") (pintype "passive"))
      (node (ref "IC4") (pin "2") (pinfunction "IN_2") (pintype "input"))
      (node (ref "IC4") (pin "4") (pinfunction "IN_4") (pintype "input"))
    )
    (net (code "10") (name "/RES") (class "Default")
      (node (ref "C28") (pin "2") (pinfunction "2_2") (pintype "passive"))
      (node (ref "IC2") (pin "4") (pinfunction "4.LLD_4") (pintype "input"))
      (node (ref "R44") (pin "1") (pinfunction "1_1") (pintype "passive"))
    )
    (net (code "11") (name "/VAUX_DC") (class "Default")
      (node (ref "C110") (pin "2") (pinfunction "2_2") (pintype "passive"))
      (node (ref "C20") (pin "+") (pinfunction "+_+") (pintype "passive"))
      (node (ref "D6") (pin "C") (pinfunction "C_C") (pintype "passive"))
      (node (ref "D7") (pin "C") (pinfunction "C_C") (pintype "passive"))
      (node (ref "R193") (pin "2") (pinfunction "2_2") (pintype "passive"))
      (node (ref "R35") (pin "2") (pinfunction "2_2") (pintype "passive"))
      (node (ref "U2") (pin "5") (pinfunction "VIN_5") (pintype "bidirectional"))
    )
    (net (code "12") (name "/VREF2.1") (class "Default")
      (node (ref "IC3") (pin "1") (pinfunction "VREF_1") (pintype "bidirectional"))
      (node (ref "IC3") (pin "5") (pinfunction "CV+_5") (pintype "input"))
      (node (ref "R61") (pin "2") (pinfunction "2_2") (pintype "passive"))
    )
    (net (code "13") (name "/V_FB2") (class "Default")
      (node (ref "C78") (pin "1") (pinfunction "1_1") (pintype "passive"))
      (node (ref "R134") (pin "1") (pinfunction "1_1") (pintype "passive"))
      (node (ref "R135") (pin "2") (pinfunction "2_2") (pintype "passive"))
      (node (ref "U2") (pin "3") (pinfunction "FB_3") (pintype "bidirectional"))
    )
    (net (code "14") (name "/V_SUPPLY") (class "Default")
      (node (ref "C33") (pin "2") (pinfunction "2_2") (pintype "passive"))
      (node (ref "C34") (pin "2") (pinfunction "2_2") (pintype "passive"))
      (node (ref "C61") (pin "1") (pinfunction "1_1") (pintype "passive"))
      (node (ref "C69") (pin "2") (pinfunction "2_2") (pintype "passive"))
      (node (ref "C79") (pin "2") (pinfunction "2_2") (pintype "passive"))
      (node (ref "C98") (pin "2") (pinfunction "2_2") (pintype "passive"))
      (node (ref "D10") (pin "C") (pinfunction "C_C") (pintype "passive"))
      (node (ref "D8") (pin "A") (pinfunction "A_A") (pintype "passive"))
      (node (ref "IC2") (pin "1") (pinfunction "1.VCC_1") (pintype "power_in"))
      (node (ref "IC9") (pin "8") (pinfunction "V+_8") (pintype "power_in"))
      (node (ref "L5") (pin "1") (pinfunction "2_1") (pintype "passive"))
      (node (ref "OC1") (pin "1") (pinfunction "1_1") (pintype "passive"))
      (node (ref "R107") (pin "2") (pinfunction "2_2") (pintype "passive"))
      (node (ref "R133") (pin "2") (pinfunction "2_2") (pintype "passive"))
      (node (ref "R69") (pin "1") (pinfunction "1_1") (pintype "passive"))
      (node (ref "R88") (pin "2") (pinfunction "2_2") (pintype "passive"))
      (node (ref "R92") (pin "1") (pinfunction "1_1") (pintype "passive"))
      (node (ref "RL1") (pin "2") (pinfunction "2_2") (pintype "passive"))
    )
    (net (code "15") (name "BOOST_INP") (class "Default")
      (node (ref "C63") (pin "1") (pinfunction "1_1") (pintype "passive"))
      (node (ref "R91") (pin "1") (pinfunction "1_1") (pintype "passive"))
      (node (ref "TP1") (pin "TP") (pinfunction "TP_TP") (pintype "input"))
      (node (ref "U1") (pin "15") (pinfunction "PA5_15") (pintype "bidirectional"))
    )
    (net (code "16") (name "CUT_OFF_OUTPUT") (class "Default")
      (node (ref "C71") (pin "1") (pinfunction "1_1") (pintype "passive"))
      (node (ref "D14") (pin "A") (pinfunction "A_A") (pintype "passive"))
      (node (ref "R110") (pin "1") (pinfunction "1_1") (pintype "passive"))
      (node (ref "U1") (pin "16") (pinfunction "PA6_16") (pintype "bidirectional"))
    )
    (net (code "17") (name "EARTH") (class "Default")
      (node (ref "C1") (pin "1") (pinfunction "1_1") (pintype "passive"))
      (node (ref "C11") (pin "1") (pinfunction "1_1") (pintype "passive"))
      (node (ref "C2") (pin "1") (pinfunction "1_1") (pintype "passive"))
      (node (ref "C25") (pin "1") (pinfunction "1_1") (pintype "passive"))
      (node (ref "C27") (pin "1") (pinfunction "1_1") (pintype "passive"))
      (node (ref "C35") (pin "2") (pinfunction "2_2") (pintype "passive"))
      (node (ref "C4") (pin "1") (pinfunction "1_1") (pintype "passive"))
      (node (ref "C5") (pin "2") (pinfunction "2_2") (pintype "passive"))
      (node (ref "C59") (pin "1") (pinfunction "1_1") (pintype "passive"))
      (node (ref "C7") (pin "1") (pinfunction "1_1") (pintype "passive"))
      (node (ref "C73") (pin "2") (pinfunction "2_2") (pintype "passive"))
      (node (ref "C74") (pin "2") (pinfunction "2_2") (pintype "passive"))
      (node (ref "C75") (pin "1") (pinfunction "1_1") (pintype "passive"))
      (node (ref "X1") (pin "3") (pinfunction "1_3") (pintype "passive"))
    )
    (net (code "18") (name "GND") (class "Default")
      (node (ref "B1") (pin "-") (pinfunction "-_-") (pintype "passive"))
      (node (ref "C10") (pin "-") (pinfunction "-_-") (pintype "passive"))
      (node (ref "C12") (pin "-") (pinfunction "-_-") (pintype "passive"))
      (node (ref "C13") (pin "-") (pinfunction "-_-") (pintype "passive"))
      (node (ref "C14") (pin "2") (pinfunction "2_2") (pintype "passive"))
      (node (ref "C15") (pin "2") (pinfunction "2_2") (pintype "passive"))
      (node (ref "C18") (pin "P$2") (pinfunction "2_P$2") (pintype "passive"))
      (node (ref "C29") (pin "1") (pinfunction "1_1") (pintype "passive"))
      (node (ref "C59") (pin "2") (pinfunction "2_2") (pintype "passive"))
      (node (ref "C6") (pin "2") (pinfunction "2_2") (pintype "passive"))
      (node (ref "C7") (pin "2") (pinfunction "2_2") (pintype "passive"))
      (node (ref "C76") (pin "2") (pinfunction "2_2") (pintype "passive"))
      (node (ref "C8") (pin "2") (pinfunction "2_2") (pintype "passive"))
      (node (ref "C82") (pin "2") (pinfunction "2_2") (pintype "passive"))
      (node (ref "C9") (pin "1") (pinfunction "1_1") (pintype "passive"))
      (node (ref "IC1") (pin "4") (pinfunction "GND_4") (pintype "power_in"))
      (node (ref "OC1") (pin "3") (pinfunction "3_3") (pintype "passive"))
      (node (ref "OC2") (pin "3") (pinfunction "3_3") (pintype "passive"))
      (node (ref "R10") (pin "1") (pinfunction "1_1") (pintype "passive"))
      (node (ref "R118") (pin "1") (pinfunction "1_1") (pintype "passive"))
      (node (ref "R119") (pin "1") (pinfunction "1_1") (pintype "passive"))
      (node (ref "R5") (pin "1") (pinfunction "1_1") (pintype "passive"))
      (node (ref "TRF1") (pin "14") (pinfunction "7_14") (pintype "passive"))
      (node (ref "TRF1") (pin "33") (pinfunction "7_33") (pintype "passive"))
      (node (ref "TRF1") (pin "48") (pinfunction "8_48") (pintype "passive"))
      (node (ref "TRF1") (pin "49") (pinfunction "7_49") (pintype "passive"))
      (node (ref "TRF1") (pin "6") (pinfunction "7_6") (pintype "passive"))
      (node (ref "Z1") (pin "1") (pinfunction "A_1") (pintype "passive"))
    )
    (net (code "19") (name "GNDA") (class "Default")
      (node (ref "C110") (pin "1") (pinfunction "1_1") (pintype "passive"))
      (node (ref "C20") (pin "-") (pinfunction "-_-") (pintype "passive"))
      (node (ref "C22") (pin "P$1") (pinfunction "1_P$1") (pintype "passive"))
      (node (ref "C23") (pin "2") (pinfunction "2_2") (pintype "passive"))
      (node (ref "C26") (pin "2") (pinfunction "2_2") (pintype "passive"))
      (node (ref "C28") (pin "1") (pinfunction "1_1") (pintype "passive"))
      (node (ref "C30") (pin "1") (pinfunction "1_1") (pintype "passive"))
      (node (ref "C31") (pin "2") (pinfunction "2_2") (pintype "passive"))
      (node (ref "C32") (pin "2") (pinfunction "2_2") (pintype "passive"))
      (node (ref "C33") (pin "1") (pinfunction "1_1") (pintype "passive"))
      (node (ref "C34") (pin "1") (pinfunction "1_1") (pintype "passive"))
      (node (ref "C35") (pin "1") (pinfunction "1_1") (pintype "passive"))
      (node (ref "C36") (pin "2") (pinfunction "2_2") (pintype "passive"))
      (node (ref "C37") (pin "2") (pinfunction "2_2") (pintype "passive"))
      (node (ref "C38") (pin "2") (pinfunction "2_2") (pintype "passive"))
      (node (ref "C39") (pin "2") (pinfunction "2_2") (pintype "passive"))
      (node (ref "C40") (pin "-") (pinfunction "-_-") (pintype "passive"))
      (node (ref "C40") (pin "-1") (pinfunction "-_-1") (pintype "passive"))
      (node (ref "C41") (pin "2") (pinfunction "2_2") (pintype "passive"))
      (node (ref "C42") (pin "-") (pinfunction "-_-") (pintype "passive"))
      (node (ref "C43") (pin "1") (pinfunction "1_1") (pintype "passive"))
      (node (ref "C44") (pin "2") (pinfunction "2_2") (pintype "passive"))
      (node (ref "C45") (pin "2") (pinfunction "2_2") (pintype "passive"))
      (node (ref "C47") (pin "2") (pinfunction "2_2") (pintype "passive"))
      (node (ref "C48") (pin "2") (pinfunction "2_2") (pintype "passive"))
      (node (ref "C49") (pin "2") (pinfunction "2_2") (pintype "passive"))
      (node (ref "C51") (pin "2") (pinfunction "2_2") (pintype "passive"))
      (node (ref "C53") (pin "2") (pinfunction "2_2") (pintype "passive"))
      (node (ref "C54") (pin "2") (pinfunction "2_2") (pintype "passive"))
      (node (ref "C55") (pin "2") (pinfunction "2_2") (pintype "passive"))
      (node (ref "C57") (pin "2") (pinfunction "2_2") (pintype "passive"))
      (node (ref "C60") (pin "1") (pinfunction "1_1") (pintype "passive"))
      (node (ref "C61") (pin "2") (pinfunction "2_2") (pintype "passive"))
      (node (ref "C62") (pin "1") (pinfunction "1_1") (pintype "passive"))
      (node (ref "C63") (pin "2") (pinfunction "2_2") (pintype "passive"))
      (node (ref "C64") (pin "2") (pinfunction "2_2") (pintype "passive"))
      (node (ref "C65") (pin "1") (pinfunction "1_1") (pintype "passive"))
      (node (ref "C66") (pin "2") (pinfunction "2_2") (pintype "passive"))
      (node (ref "C67") (pin "2") (pinfunction "2_2") (pintype "passive"))
      (node (ref "C68") (pin "1") (pinfunction "1_1") (pintype "passive"))
      (node (ref "C69") (pin "1") (pinfunction "1_1") (pintype "passive"))
      (node (ref "C70") (pin "1") (pinfunction "1_1") (pintype "passive"))
      (node (ref "C72") (pin "1") (pinfunction "1_1") (pintype "passive"))
      (node (ref "C75") (pin "2") (pinfunction "2_2") (pintype "passive"))
      (node (ref "C78") (pin "2") (pinfunction "2_2") (pintype "passive"))
      (node (ref "C79") (pin "1") (pinfunction "1_1") (pintype "passive"))
      (node (ref "C84") (pin "-") (pinfunction "-_-") (pintype "passive"))
      (node (ref "C84_X") (pin "-") (pinfunction "-_-") (pintype "passive"))
      (node (ref "C85") (pin "2") (pinfunction "2_2") (pintype "passive"))
      (node (ref "C98") (pin "1") (pinfunction "1_1") (pintype "passive"))
      (node (ref "D12") (pin "A1") (pinfunction "A1_A1") (pintype "passive"))
      (node (ref "D13") (pin "1") (pinfunction "A_1") (pintype "passive"))
      (node (ref "D18") (pin "A") (pinfunction "A_A") (pintype "passive"))
      (node (ref "H2") (pin "1") (pinfunction "P$1_1") (pintype "bidirectional"))
      (node (ref "H2") (pin "2") (pinfunction "P$1_2") (pintype "bidirectional"))
      (node (ref "H2") (pin "3") (pinfunction "P$2_3") (pintype "bidirectional"))
      (node (ref "H2") (pin "4") (pinfunction "P$2_4") (pintype "bidirectional"))
      (node (ref "IC2") (pin "5") (pinfunction "5.TRIG_5") (pintype "output"))
      (node (ref "IC2") (pin "7") (pinfunction "7.GND_7") (pintype "input"))
      (node (ref "IC4") (pin "1") (pinfunction "GND_1") (pintype "input"))
      (node (ref "IC5") (pin "4") (pinfunction "V-_4") (pintype "power_in"))
      (node (ref "IC6") (pin "A") (pinfunction "1_A") (pintype "passive"))
      (node (ref "IC9") (pin "4") (pinfunction "V-_4") (pintype "power_in"))
      (node (ref "L2") (pin "1") (pinfunction "1.GND_1") (pintype "passive"))
      (node (ref "L2") (pin "4") (pinfunction "4.GND_4") (pintype "passive"))
      (node (ref "PROG1") (pin "3") (pinfunction "GND_3") (pintype "passive"))
      (node (ref "PROG2") (pin "3") (pinfunction "GND_3") (pintype "passive"))
      (node (ref "Q2") (pin "S") (pinfunction "S_S") (pintype "passive"))
      (node (ref "R102") (pin "1") (pinfunction "1_1") (pintype "passive"))
      (node (ref "R135") (pin "1") (pinfunction "1_1") (pintype "passive"))
      (node (ref "R25") (pin "2") (pinfunction "2_2") (pintype "passive"))
      (node (ref "R26") (pin "2") (pinfunction "2_2") (pintype "passive"))
      (node (ref "R38") (pin "2") (pinfunction "2_2") (pintype "passive"))
      (node (ref "R39") (pin "2") (pinfunction "2_2") (pintype "passive"))
      (node (ref "R40") (pin "2") (pinfunction "2_2") (pintype "passive"))
      (node (ref "R41") (pin "2") (pinfunction "2_2") (pintype "passive"))
      (node (ref "R42") (pin "2") (pinfunction "2_2") (pintype "passive"))
      (node (ref "R43") (pin "2") (pinfunction "2_2") (pintype "passive"))
      (node (ref "R44") (pin "2") (pinfunction "2_2") (pintype "passive"))
      (node (ref "R47") (pin "2") (pinfunction "2_2") (pintype "passive"))
      (node (ref "R48") (pin "2") (pinfunction "2_2") (pintype "passive"))
      (node (ref "R51") (pin "2") (pinfunction "2_2") (pintype "passive"))
      (node (ref "R56") (pin "1") (pinfunction "1_1") (pintype "passive"))
      (node (ref "R58") (pin "2") (pinfunction "2_2") (pintype "passive"))
      (node (ref "R64") (pin "1") (pinfunction "1_1") (pintype "passive"))
      (node (ref "R65") (pin "1") (pinfunction "1_1") (pintype "passive"))
      (node (ref "R68") (pin "1") (pinfunction "1_1") (pintype "passive"))
      (node (ref "R73") (pin "2") (pinfunction "2_2") (pintype "passive"))
      (node (ref "R75") (pin "1") (pinfunction "1_1") (pintype "passive"))
      (node (ref "R81") (pin "2") (pinfunction "2_2") (pintype "passive"))
      (node (ref "R82") (pin "2") (pinfunction "2_2") (pintype "passive"))
      (node (ref "R87") (pin "1") (pinfunction "1_1") (pintype "passive"))
      (node (ref "R90") (pin "1") (pinfunction "1_1") (pintype "passive"))
      (node (ref "R99") (pin "1") (pinfunction "1_1") (pintype "passive"))
      (node (ref "T5") (pin "2") (pinfunction "E_2") (pintype "passive"))
      (node (ref "T6") (pin "2") (pinfunction "E_2") (pintype "passive"))
      (node (ref "TRF1") (pin "24") (pinfunction "10_24") (pintype "passive"))
      (node (ref "TRF1") (pin "27") (pinfunction "10_27") (pintype "passive"))
      (node (ref "TRF1") (pin "40") (pinfunction "9_40") (pintype "passive"))
      (node (ref "TRF1") (pin "41") (pinfunction "10_41") (pintype "passive"))
      (node (ref "TRF1") (pin "6.1") (pinfunction "9_6.1") (pintype "passive"))
      (node (ref "TRF1") (pin "6.2") (pinfunction "9_6.2") (pintype "passive"))
      (node (ref "TRF1") (pin "6.5") (pinfunction "9_6.5") (pintype "passive"))
      (node (ref "TRF1") (pin "7") (pinfunction "10_7") (pintype "passive"))
      (node (ref "TVS1") (pin "A") (pinfunction "1_A") (pintype "passive"))
      (node (ref "U1") (pin "23") (pinfunction "VSS.._23") (pintype "bidirectional"))
      (node (ref "U1") (pin "35") (pinfunction "VSS_35") (pintype "bidirectional"))
      (node (ref "U1") (pin "47") (pinfunction "VSS._47") (pintype "bidirectional"))
      (node (ref "U1") (pin "8") (pinfunction "VSSA_8") (pintype "bidirectional"))
      (node (ref "U2") (pin "2") (pinfunction "GND_2") (pintype "bidirectional"))
      (node (ref "X2") (pin "GND") (pinfunction "GND_GND") (pintype "bidirectional"))
      (node (ref "X2") (pin "SHLD1") (pinfunction "1_SHLD1") (pintype "bidirectional"))
      (node (ref "X2") (pin "SHLD2") (pinfunction "2_SHLD2") (pintype "bidirectional"))
      (node (ref "X4") (pin "1") (pinfunction "1_1") (pintype "passive"))
      (node (ref "Z4") (pin "1") (pinfunction "A_1") (pintype "passive"))
      (node (ref "Z6") (pin "1") (pinfunction "A_1") (pintype "passive"))
    )
    (net (code "20") (name "GNDIO") (class "Default")
      (node (ref "D15") (pin "C") (pinfunction "C_C") (pintype "passive"))
      (node (ref "IC8") (pin "D") (pinfunction "D5678_D") (pintype "passive"))
      (node (ref "IC8") (pin "D1") (pinfunction "D5678_D1") (pintype "passive"))
      (node (ref "IC8") (pin "D2") (pinfunction "D5678_D2") (pintype "passive"))
      (node (ref "IC8") (pin "D3") (pinfunction "D5678_D3") (pintype "passive"))
      (node (ref "IC8") (pin "P$1") (pinfunction "D5678_P$1") (pintype "passive"))
      (node (ref "IC8") (pin "P$2") (pinfunction "D5678_P$2") (pintype "passive"))
      (node (ref "IC8") (pin "P$3") (pinfunction "D5678_P$3") (pintype "passive"))
      (node (ref "R57") (pin "1") (pinfunction "1_1") (pintype "passive"))
      (node (ref "T10") (pin "E") (pinfunction "E_E") (pintype "passive"))
      (node (ref "X3") (pin "2") (pinfunction "1_2") (pintype "passive"))
    )
    (net (code "21") (name "I_OUT_ADC") (class "Default")
      (node (ref "C62") (pin "2") (pinfunction "2_2") (pintype "passive"))
      (node (ref "R83") (pin "2") (pinfunction "2_2") (pintype "passive"))
      (node (ref "U1") (pin "17") (pinfunction "PA7_17") (pintype "bidirectional"))
    )
    (net (code "22") (name "I_PWM") (class "Default")
      (node (ref "R55") (pin "2") (pinfunction "2_2") (pintype "passive"))
      (node (ref "U1") (pin "18") (pinfunction "PB0_18") (pintype "bidirectional"))
    )
    (net (code "23") (name "JTDO") (class "Default")
      (node (ref "PROG1") (pin "6") (pinfunction "PRG_SWO_6") (pintype "passive"))
      (node (ref "PROG2") (pin "6") (pinfunction "PRG_SWO_6") (pintype "passive"))
      (node (ref "U1") (pin "39") (pinfunction "PB3_39") (pintype "bidirectional"))
    )
    (net (code "24") (name "LED_B") (class "Default")
      (node (ref "R52") (pin "1") (pinfunction "1_1") (pintype "passive"))
      (node (ref "U1") (pin "41") (pinfunction "PB5_41") (pintype "bidirectional"))
    )
    (net (code "25") (name "LED_G") (class "Default")
      (node (ref "R53") (pin "1") (pinfunction "1_1") (pintype "passive"))
      (node (ref "U1") (pin "40") (pinfunction "PB4_40") (pintype "bidirectional"))
    )
    (net (code "26") (name "LED_R") (class "Default")
      (node (ref "R49") (pin "1") (pinfunction "1_1") (pintype "passive"))
      (node (ref "U1") (pin "42") (pinfunction "PB6_42") (pintype "bidirectional"))
    )
    (net (code "27") (name "NRST") (class "Default")
      (node (ref "C30") (pin "2") (pinfunction "2_2") (pintype "passive"))
      (node (ref "PROG1") (pin "5") (pinfunction "NRST_5") (pintype "passive"))
      (node (ref "PROG2") (pin "5") (pinfunction "NRST_5") (pintype "passive"))
      (node (ref "R46") (pin "2") (pinfunction "2_2") (pintype "passive"))
      (node (ref "U1") (pin "7") (pinfunction "NRST_7") (pintype "bidirectional"))
    )
    (net (code "28") (name "Net-(B1-PadAC1)") (class "Default")
      (node (ref "B1") (pin "AC1") (pinfunction "AC1_AC1") (pintype "passive"))
      (node (ref "C4") (pin "2") (pinfunction "2_2") (pintype "passive"))
      (node (ref "C83") (pin "2") (pinfunction "2_2") (pintype "passive"))
      (node (ref "C83") (pin "4") (pinfunction "2_4") (pintype "passive"))
      (node (ref "L1") (pin "4") (pinfunction "4_4") (pintype "passive"))
      (node (ref "L1") (pin "7") (pinfunction "4_7") (pintype "passive"))
    )
    (net (code "29") (name "Net-(B1-PadAC2)") (class "Default")
      (node (ref "B1") (pin "AC2") (pinfunction "AC2_AC2") (pintype "passive"))
      (node (ref "C5") (pin "1") (pinfunction "1_1") (pintype "passive"))
      (node (ref "C83") (pin "1") (pinfunction "1_1") (pintype "passive"))
      (node (ref "C83") (pin "3") (pinfunction "1_3") (pintype "passive"))
      (node (ref "L1") (pin "2") (pinfunction "2_2") (pintype "passive"))
      (node (ref "L1") (pin "6") (pinfunction "2_6") (pintype "passive"))
    )
    (net (code "30") (name "Net-(C1-Pad2)") (class "Default")
      (node (ref "C1") (pin "2") (pinfunction "2_2") (pintype "passive"))
      (node (ref "C3") (pin "2") (pinfunction "2_2") (pintype "passive"))
      (node (ref "C3") (pin "4") (pinfunction "2_4") (pintype "passive"))
      (node (ref "C3") (pin "6") (pinfunction "2_6") (pintype "passive"))
      (node (ref "L1") (pin "3") (pinfunction "3_3") (pintype "passive"))
      (node (ref "L1") (pin "8") (pinfunction "3_8") (pintype "passive"))
      (node (ref "NTC1") (pin "P$1") (pinfunction "1_P$1") (pintype "passive"))
      (node (ref "NTC1") (pin "P$4") (pinfunction "1_P$4") (pintype "passive"))
      (node (ref "R1") (pin "1") (pinfunction "1_1") (pintype "passive"))
      (node (ref "R2") (pin "1") (pinfunction "1_1") (pintype "passive"))
    )
    (net (code "31") (name "Net-(C16-Pad1)") (class "Default")
      (node (ref "C16") (pin "1") (pinfunction "1_1") (pintype "passive"))
      (node (ref "D1") (pin "C") (pinfunction "C_C") (pintype "passive"))
      (node (ref "R13") (pin "2") (pinfunction "2_2") (pintype "passive"))
    )
    (net (code "32") (name "Net-(C16-Pad2)") (class "Default")
      (node (ref "C16") (pin "2") (pinfunction "2_2") (pintype "passive"))
      (node (ref "R19") (pin "1") (pinfunction "1_1") (pintype "passive"))
    )
    (net (code "33") (name "Net-(C17-1-Pad3)") (class "Default")
      (node (ref "C17") (pin "1") (pinfunction "1_1") (pintype "passive"))
      (node (ref "C17") (pin "3") (pinfunction "1_3") (pintype "passive"))
      (node (ref "D4") (pin "A") (pinfunction "A_A") (pintype "passive"))
      (node (ref "Q1") (pin "D") (pinfunction "D_D") (pintype "passive"))
      (node (ref "TRF1") (pin "55") (pinfunction "1_55") (pintype "passive"))
      (node (ref "TRF1") (pin "56") (pinfunction "1_56") (pintype "passive"))
      (node (ref "TRF1") (pin "57") (pinfunction "1_57") (pintype "passive"))
      (node (ref "TRF1") (pin "58") (pinfunction "1_58") (pintype "passive"))
    )
    (net (code "34") (name "Net-(C17-2-Pad4)") (class "Default")
      (node (ref "C17") (pin "2") (pinfunction "2_2") (pintype "passive"))
      (node (ref "C17") (pin "4") (pinfunction "2_4") (pintype "passive"))
      (node (ref "R31") (pin "1") (pinfunction "1_1") (pintype "passive"))
    )
    (net (code "35") (name "Net-(C19-Pad1)") (class "Default")
      (node (ref "C19") (pin "1") (pinfunction "1_1") (pintype "passive"))
      (node (ref "R35") (pin "1") (pinfunction "1_1") (pintype "passive"))
    )
    (net (code "36") (name "Net-(C19-Pad2)") (class "Default")
      (node (ref "C19") (pin "2") (pinfunction "2_2") (pintype "passive"))
      (node (ref "D6") (pin "A") (pinfunction "A_A") (pintype "passive"))
      (node (ref "R22") (pin "1") (pinfunction "1_1") (pintype "passive"))
    )
    (net (code "37") (name "Net-(C21-Pad2)") (class "Default")
      (node (ref "C21") (pin "2") (pinfunction "2_2") (pintype "passive"))
      (node (ref "R25") (pin "1") (pinfunction "1_1") (pintype "passive"))
      (node (ref "R26") (pin "1") (pinfunction "1_1") (pintype "passive"))
      (node (ref "R39") (pin "1") (pinfunction "1_1") (pintype "passive"))
      (node (ref "R40") (pin "1") (pinfunction "1_1") (pintype "passive"))
      (node (ref "R41") (pin "1") (pinfunction "1_1") (pintype "passive"))
      (node (ref "R42") (pin "1") (pinfunction "1_1") (pintype "passive"))
      (node (ref "R43") (pin "1") (pinfunction "1_1") (pintype "passive"))
    )
    (net (code "38") (name "Net-(C24-2)") (class "Default")
      (node (ref "B1") (pin "+") (pinfunction "+_+") (pintype "passive"))
      (node (ref "C11") (pin "2") (pinfunction "2_2") (pintype "passive"))
      (node (ref "C12") (pin "+") (pinfunction "+_+") (pintype "passive"))
      (node (ref "C24") (pin "P$2") (pinfunction "2_P$2") (pintype "passive"))
      (node (ref "C27") (pin "2") (pinfunction "2_2") (pintype "passive"))
      (node (ref "C76") (pin "1") (pinfunction "1_1") (pintype "passive"))
      (node (ref "C82") (pin "1") (pinfunction "1_1") (pintype "passive"))
      (node (ref "D2") (pin "A") (pinfunction "A_A") (pintype "passive"))
      (node (ref "D3") (pin "A") (pinfunction "A_A") (pintype "passive"))
      (node (ref "R11") (pin "2") (pinfunction "2_2") (pintype "passive"))
      (node (ref "R9") (pin "2") (pinfunction "2_2") (pintype "passive"))
      (node (ref "TRF1") (pin "16") (pinfunction "4_16") (pintype "passive"))
      (node (ref "TRF1") (pin "3") (pinfunction "4_3") (pintype "passive"))
      (node (ref "TRF1") (pin "35") (pinfunction "4_35") (pintype "passive"))
      (node (ref "TRF1") (pin "52") (pinfunction "4_52") (pintype "passive"))
    )
    (net (code "39") (name "Net-(C43-Pad2)") (class "Default")
      (node (ref "C43") (pin "2") (pinfunction "2_2") (pintype "passive"))
      (node (ref "R60") (pin "2") (pinfunction "2_2") (pintype "passive"))
      (node (ref "R62") (pin "2") (pinfunction "2_2") (pintype "passive"))
    )
    (net (code "40") (name "Net-(C52-Pad1)") (class "Default")
      (node (ref "C52") (pin "1") (pinfunction "1_1") (pintype "passive"))
      (node (ref "R70") (pin "1") (pinfunction "1_1") (pintype "passive"))
    )
    (net (code "41") (name "Net-(C56-Pad1)") (class "Default")
      (node (ref "C56") (pin "1") (pinfunction "1_1") (pintype "passive"))
      (node (ref "R76") (pin "1") (pinfunction "1_1") (pintype "passive"))
    )
    (net (code "42") (name "Net-(C68-Pad2)") (class "Default")
      (node (ref "C68") (pin "2") (pinfunction "2_2") (pintype "passive"))
      (node (ref "R103") (pin "1") (pinfunction "1_1") (pintype "passive"))
      (node (ref "R104") (pin "2") (pinfunction "2_2") (pintype "passive"))
    )
    (net (code "43") (name "Net-(C77-Pad1)") (class "Default")
      (node (ref "C77") (pin "1") (pinfunction "1_1") (pintype "passive"))
      (node (ref "R194") (pin "2") (pinfunction "2_2") (pintype "passive"))
    )
    (net (code "44") (name "Net-(C84-Pad+)") (class "Default")
      (node (ref "C84") (pin "+") (pinfunction "+_+") (pintype "passive"))
      (node (ref "C84_X") (pin "+") (pinfunction "+_+") (pintype "passive"))
      (node (ref "C85") (pin "1") (pinfunction "1_1") (pintype "passive"))
      (node (ref "L6") (pin "2") (pinfunction "2_2") (pintype "passive"))
      (node (ref "X3") (pin "1") (pinfunction "1_1") (pintype "passive"))
    )
    (net (code "45") (name "Net-(D1-PadA)") (class "Default")
      (node (ref "D1") (pin "A") (pinfunction "A_A") (pintype "passive"))
      (node (ref "R19") (pin "2") (pinfunction "2_2") (pintype "passive"))
      (node (ref "R20") (pin "2") (pinfunction "2_2") (pintype "passive"))
    )
    (net (code "46") (name "Net-(D2-PadC)") (class "Default")
      (node (ref "D2") (pin "C") (pinfunction "C_C") (pintype "passive"))
      (node (ref "R17") (pin "1") (pinfunction "1_1") (pintype "passive"))
      (node (ref "R18") (pin "1") (pinfunction "1_1") (pintype "passive"))
    )
    (net (code "47") (name "Net-(D3-PadC)") (class "Default")
      (node (ref "D3") (pin "C") (pinfunction "C_C") (pintype "passive"))
      (node (ref "R23") (pin "1") (pinfunction "1_1") (pintype "passive"))
      (node (ref "R24") (pin "1") (pinfunction "1_1") (pintype "passive"))
    )
    (net (code "48") (name "Net-(D4-PadC)") (class "Default")
      (node (ref "D4") (pin "C") (pinfunction "C_C") (pintype "passive"))
      (node (ref "R17") (pin "2") (pinfunction "2_2") (pintype "passive"))
      (node (ref "R18") (pin "2") (pinfunction "2_2") (pintype "passive"))
      (node (ref "R23") (pin "2") (pinfunction "2_2") (pintype "passive"))
      (node (ref "R24") (pin "2") (pinfunction "2_2") (pintype "passive"))
    )
    (net (code "49") (name "Net-(D5-PadA)") (class "Default")
      (node (ref "D5") (pin "A") (pinfunction "A_A") (pintype "passive"))
      (node (ref "Q1") (pin "G") (pinfunction "G_G") (pintype "passive"))
      (node (ref "R14") (pin "1") (pinfunction "1_1") (pintype "passive"))
      (node (ref "R21") (pin "2") (pinfunction "2_2") (pintype "passive"))
    )
    (net (code "50") (name "Net-(D5-PadC)") (class "Default")
      (node (ref "D5") (pin "C") (pinfunction "C_C") (pintype "passive"))
      (node (ref "R14") (pin "2") (pinfunction "2_2") (pintype "passive"))
      (node (ref "R15") (pin "1") (pinfunction "1_1") (pintype "passive"))
    )
    (net (code "51") (name "Net-(D9-A1)") (class "Default")
      (node (ref "C64") (pin "1") (pinfunction "1_1") (pintype "passive"))
      (node (ref "D9") (pin "1") (pinfunction "A1_1") (pintype "passive"))
      (node (ref "D9") (pin "2") (pinfunction "A2_2") (pintype "passive"))
      (node (ref "R85") (pin "1") (pinfunction "1_1") (pintype "passive"))
      (node (ref "TVS1") (pin "C") (pinfunction "2_C") (pintype "passive"))
    )
    (net (code "52") (name "Net-(D11-PadA)") (class "Default")
      (node (ref "D11") (pin "A") (pinfunction "A_A") (pintype "passive"))
      (node (ref "R93") (pin "1") (pinfunction "1_1") (pintype "passive"))
    )
    (net (code "53") (name "Net-(D15-PadA)") (class "Default")
      (node (ref "D15") (pin "A") (pinfunction "A_A") (pintype "passive"))
      (node (ref "R117") (pin "2") (pinfunction "2_2") (pintype "passive"))
      (node (ref "T10") (pin "B") (pinfunction "B_B") (pintype "passive"))
    )
    (net (code "54") (name "Net-(F1_X1-1)") (class "Default")
      (node (ref "C2") (pin "2") (pinfunction "2_2") (pintype "passive"))
      (node (ref "C3") (pin "1") (pinfunction "1_1") (pintype "passive"))
      (node (ref "C3") (pin "3") (pinfunction "1_3") (pintype "passive"))
      (node (ref "C3") (pin "5") (pinfunction "1_5") (pintype "passive"))
      (node (ref "F1") (pin "1") (pinfunction "1_1") (pintype "passive"))
      (node (ref "F1_X1") (pin "P$1") (pinfunction "1_P$1") (pintype "passive"))
      (node (ref "F1_X2") (pin "P$1") (pinfunction "1_P$1") (pintype "passive"))
      (node (ref "F1_X3") (pin "P$1") (pinfunction "1_P$1") (pintype "passive"))
      (node (ref "F1_X4") (pin "P$1") (pinfunction "1_P$1") (pintype "passive"))
      (node (ref "F1_X5") (pin "P$1") (pinfunction "1_P$1") (pintype "passive"))
      (node (ref "F1_X6") (pin "P$2") (pinfunction "2_P$2") (pintype "passive"))
      (node (ref "L1") (pin "1") (pinfunction "1_1") (pintype "passive"))
      (node (ref "L1") (pin "5") (pinfunction "1_5") (pintype "passive"))
      (node (ref "R1") (pin "2") (pinfunction "2_2") (pintype "passive"))
      (node (ref "R4") (pin "2") (pinfunction "2_2") (pintype "passive"))
    )
    (net (code "55") (name "Net-(F1_X1-2)") (class "Default")
      (node (ref "F1") (pin "2") (pinfunction "2_2") (pintype "passive"))
      (node (ref "F1_X1") (pin "P$2") (pinfunction "2_P$2") (pintype "passive"))
      (node (ref "F1_X2") (pin "P$2") (pinfunction "2_P$2") (pintype "passive"))
      (node (ref "F1_X3") (pin "P$2") (pinfunction "2_P$2") (pintype "passive"))
      (node (ref "F1_X4") (pin "P$2") (pinfunction "2_P$2") (pintype "passive"))
      (node (ref "F1_X5") (pin "P$2") (pinfunction "2_P$2") (pintype "passive"))
      (node (ref "F1_X6") (pin "P$1") (pinfunction "1_P$1") (pintype "passive"))
      (node (ref "X1") (pin "2") (pinfunction "1_2") (pintype "passive"))
    )
    (net (code "56") (name "Net-(IC1-CS)") (class "Default")
      (node (ref "C9") (pin "2") (pinfunction "2_2") (pintype "passive"))
      (node (ref "IC1") (pin "3") (pinfunction "CS_3") (pintype "input"))
      (node (ref "R6") (pin "1") (pinfunction "1_1") (pintype "passive"))
    )
    (net (code "57") (name "Net-(IC1-DRV)") (class "Default")
      (node (ref "IC1") (pin "5") (pinfunction "DRV_5") (pintype "output"))
      (node (ref "R15") (pin "2") (pinfunction "2_2") (pintype "passive"))
    )
    (net (code "58") (name "Net-(IC1-FAULT)") (class "Default")
      (node (ref "C6") (pin "1") (pinfunction "1_1") (pintype "passive"))
      (node (ref "IC1") (pin "1") (pinfunction "FAULT_1") (pintype "power_in"))
      (node (ref "R5") (pin "2") (pinfunction "2_2") (pintype "passive"))
      (node (ref "Z2") (pin "1") (pinfunction "A_1") (pintype "passive"))
    )
    (net (code "59") (name "Net-(IC1-FB)") (class "Default")
      (node (ref "C8") (pin "1") (pinfunction "1_1") (pintype "passive"))
      (node (ref "IC1") (pin "2") (pinfunction "FB_2") (pintype "input"))
      (node (ref "OC1") (pin "4") (pinfunction "4_4") (pintype "passive"))
      (node (ref "OC2") (pin "4") (pinfunction "4_4") (pintype "passive"))
    )
    (net (code "60") (name "Net-(IC1-HV)") (class "Default")
      (node (ref "IC1") (pin "8") (pinfunction "HV_8") (pintype "input"))
      (node (ref "R12") (pin "2") (pinfunction "2_2") (pintype "passive"))
    )
    (net (code "61") (name "Net-(IC1-VCC)") (class "Default")
      (node (ref "C14") (pin "1") (pinfunction "1_1") (pintype "passive"))
      (node (ref "C15") (pin "1") (pinfunction "1_1") (pintype "passive"))
      (node (ref "IC1") (pin "6") (pinfunction "VCC_6") (pintype "input"))
      (node (ref "R16") (pin "2") (pinfunction "2_2") (pintype "passive"))
      (node (ref "Z2") (pin "3") (pinfunction "C_3") (pintype "passive"))
    )
    (net (code "62") (name "Net-(IC2-2.MIN_TOFF)") (class "Default")
      (node (ref "IC2") (pin "2") (pinfunction "2.MIN_TOFF_2") (pintype "input"))
      (node (ref "R48") (pin "1") (pinfunction "1_1") (pintype "passive"))
    )
    (net (code "63") (name "Net-(IC2-3.MIN_TON)") (class "Default")
      (node (ref "IC2") (pin "3") (pinfunction "3.MIN_TON_3") (pintype "input"))
      (node (ref "R47") (pin "1") (pinfunction "1_1") (pintype "passive"))
    )
    (net (code "64") (name "Net-(IC2-8.DRV)") (class "Default")
      (node (ref "IC2") (pin "8") (pinfunction "8.DRV_8") (pintype "input"))
      (node (ref "R36") (pin "1") (pinfunction "1_1") (pintype "passive"))
    )
    (net (code "65") (name "Net-(IC3-CC+)") (class "Default")
      (node (ref "C80") (pin "2") (pinfunction "2_2") (pintype "passive"))
      (node (ref "IC3") (pin "3") (pinfunction "CC+_3") (pintype "input"))
      (node (ref "R62") (pin "1") (pinfunction "1_1") (pintype "passive"))
      (node (ref "R63") (pin "2") (pinfunction "2_2") (pintype "passive"))
    )
    (net (code "66") (name "Net-(IC3-CC-)") (class "Default")
      (node (ref "C80") (pin "1") (pinfunction "1_1") (pintype "passive"))
      (node (ref "IC3") (pin "2") (pinfunction "CC-_2") (pintype "input"))
      (node (ref "R66") (pin "1") (pinfunction "1_1") (pintype "passive"))
      (node (ref "R70") (pin "2") (pinfunction "2_2") (pintype "passive"))
    )
    (net (code "67") (name "Net-(IC3-CV-)") (class "Default")
      (node (ref "IC3") (pin "4") (pinfunction "CV-_4") (pintype "input"))
      (node (ref "R76") (pin "2") (pinfunction "2_2") (pintype "passive"))
      (node (ref "R79") (pin "1") (pinfunction "1_1") (pintype "passive"))
      (node (ref "R80") (pin "2") (pinfunction "2_2") (pintype "passive"))
    )
    (net (code "68") (name "Net-(IC3-OUT)") (class "Default")
      (node (ref "C52") (pin "2") (pinfunction "2_2") (pintype "passive"))
      (node (ref "C56") (pin "2") (pinfunction "2_2") (pintype "passive"))
      (node (ref "IC3") (pin "7") (pinfunction "OUT_7") (pintype "output"))
      (node (ref "R74") (pin "1") (pinfunction "1_1") (pintype "passive"))
    )
    (net (code "69") (name "Net-(IC3-VCC)") (class "Default")
      (node (ref "C46") (pin "2") (pinfunction "2_2") (pintype "passive"))
      (node (ref "IC3") (pin "8") (pinfunction "VCC_8") (pintype "power_in"))
      (node (ref "R69") (pin "2") (pinfunction "2_2") (pintype "passive"))
    )
    (net (code "70") (name "Net-(IC5A--IN)") (class "Default")
      (node (ref "C58") (pin "1") (pinfunction "1_1") (pintype "passive"))
      (node (ref "IC5") (pin "2") (pinfunction "-IN_2") (pintype "input"))
      (node (ref "R75") (pin "2") (pinfunction "2_2") (pintype "passive"))
      (node (ref "R77") (pin "1") (pinfunction "1_1") (pintype "passive"))
    )
    (net (code "71") (name "Net-(IC5A-OUT)") (class "Default")
      (node (ref "C58") (pin "2") (pinfunction "2_2") (pintype "passive"))
      (node (ref "IC5") (pin "1") (pinfunction "OUT_1") (pintype "output"))
      (node (ref "R77") (pin "2") (pinfunction "2_2") (pintype "passive"))
      (node (ref "R83") (pin "1") (pinfunction "1_1") (pintype "passive"))
    )
    (net (code "72") (name "Net-(IC5B-+IN)") (class "Default")
      (node (ref "C81") (pin "2") (pinfunction "2_2") (pintype "passive"))
      (node (ref "IC5") (pin "5") (pinfunction "+IN_5") (pintype "input"))
      (node (ref "R67") (pin "1") (pinfunction "1_1") (pintype "passive"))
    )
    (net (code "73") (name "Net-(IC5B--IN)") (class "Default")
      (node (ref "C50") (pin "1") (pinfunction "1_1") (pintype "passive"))
      (node (ref "C81") (pin "1") (pinfunction "1_1") (pintype "passive"))
      (node (ref "IC5") (pin "6") (pinfunction "-IN_6") (pintype "input"))
      (node (ref "R68") (pin "2") (pinfunction "2_2") (pintype "passive"))
      (node (ref "R71") (pin "1") (pinfunction "1_1") (pintype "passive"))
    )
    (net (code "74") (name "Net-(IC6-2)") (class "Default")
      (node (ref "IC6") (pin "R") (pinfunction "2_R") (pintype "passive"))
      (node (ref "R89") (pin "1") (pinfunction "1_1") (pintype "passive"))
      (node (ref "R90") (pin "2") (pinfunction "2_2") (pintype "passive"))
    )
    (net (code "75") (name "Net-(IC6-3)") (class "Default")
      (node (ref "C65") (pin "2") (pinfunction "2_2") (pintype "passive"))
      (node (ref "IC6") (pin "C") (pinfunction "3_C") (pintype "passive"))
      (node (ref "IC9") (pin "3") (pinfunction "+IN_3") (pintype "input"))
      (node (ref "R88") (pin "1") (pinfunction "1_1") (pintype "passive"))
      (node (ref "R89") (pin "2") (pinfunction "2_2") (pintype "passive"))
    )
    (net (code "76") (name "Net-(IC8-G4)") (class "Default")
      (node (ref "IC8") (pin "GATE") (pinfunction "G4_GATE") (pintype "passive"))
      (node (ref "R107") (pin "1") (pinfunction "1_1") (pintype "passive"))
      (node (ref "R116") (pin "2") (pinfunction "2_2") (pintype "passive"))
      (node (ref "T7") (pin "3") (pinfunction "C_3") (pintype "passive"))
      (node (ref "T9") (pin "3") (pinfunction "C_3") (pintype "passive"))
      (node (ref "Z8") (pin "3") (pinfunction "C_3") (pintype "passive"))
    )
    (net (code "77") (name "Net-(IC9A--IN)") (class "Default")
      (node (ref "IC9") (pin "1") (pinfunction "OUT_1") (pintype "output"))
      (node (ref "IC9") (pin "2") (pinfunction "-IN_2") (pintype "input"))
      (node (ref "R101") (pin "2") (pinfunction "2_2") (pintype "passive"))
      (node (ref "R98") (pin "2") (pinfunction "2_2") (pintype "passive"))
    )
    (net (code "78") (name "Net-(IC9B-+IN)") (class "Default")
      (node (ref "D12") (pin "A") (pinfunction "A_A") (pintype "passive"))
      (node (ref "IC9") (pin "5") (pinfunction "+IN_5") (pintype "input"))
      (node (ref "R105") (pin "1") (pinfunction "1_1") (pintype "passive"))
      (node (ref "R94") (pin "2") (pinfunction "2_2") (pintype "passive"))
      (node (ref "R98") (pin "1") (pinfunction "1_1") (pintype "passive"))
    )
    (net (code "79") (name "Net-(IC9B--IN)") (class "Default")
      (node (ref "IC9") (pin "6") (pinfunction "-IN_6") (pintype "input"))
      (node (ref "R101") (pin "1") (pinfunction "1_1") (pintype "passive"))
      (node (ref "R102") (pin "2") (pinfunction "2_2") (pintype "passive"))
      (node (ref "R106") (pin "1") (pinfunction "1_1") (pintype "passive"))
    )
    (net (code "80") (name "Net-(IC9B-OUT)") (class "Default")
      (node (ref "IC9") (pin "7") (pinfunction "OUT_7") (pintype "output"))
      (node (ref "R105") (pin "2") (pinfunction "2_2") (pintype "passive"))
      (node (ref "R106") (pin "2") (pinfunction "2_2") (pintype "passive"))
      (node (ref "R108") (pin "1") (pinfunction "1_1") (pintype "passive"))
    )
    (net (code "81") (name "Net-(L2-Pad2)") (class "Default")
      (node (ref "L2") (pin "2") (pinfunction "2_2") (pintype "passive"))
      (node (ref "X2") (pin "D+") (pinfunction "D+_D+") (pintype "bidirectional"))
    )
    (net (code "82") (name "Net-(L2-Pad3)") (class "Default")
      (node (ref "L2") (pin "3") (pinfunction "3_3") (pintype "passive"))
      (node (ref "X2") (pin "D-") (pinfunction "D-_D-") (pintype "bidirectional"))
    )
    (net (code "83") (name "Net-(L2-Pad5)") (class "Default")
      (node (ref "L2") (pin "5") (pinfunction "5_5") (pintype "passive"))
      (node (ref "R97") (pin "1") (pinfunction "1_1") (pintype "passive"))
    )
    (net (code "84") (name "Net-(L2-Pad6)") (class "Default")
      (node (ref "L2") (pin "6") (pinfunction "6_6") (pintype "passive"))
      (node (ref "R96") (pin "1") (pinfunction "1_1") (pintype "passive"))
    )
    (net (code "85") (name "Net-(L5-1)") (class "Default")
      (node (ref "C77") (pin "2") (pinfunction "2_2") (pintype "passive"))
      (node (ref "D18") (pin "C") (pinfunction "C_C") (pintype "passive"))
      (node (ref "L5") (pin "2") (pinfunction "1_2") (pintype "passive"))
      (node (ref "U2") (pin "6") (pinfunction "LX_6") (pintype "bidirectional"))
    )
    (net (code "86") (name "Net-(LED1-Pad1)") (class "Default")
      (node (ref "LED1") (pin "1") (pinfunction "1_1") (pintype "passive"))
      (node (ref "R49") (pin "2") (pinfunction "2_2") (pintype "passive"))
    )
    (net (code "87") (name "Net-(LED1-Pad3)") (class "Default")
      (node (ref "LED1") (pin "3") (pinfunction "3_3") (pintype "passive"))
      (node (ref "R53") (pin "2") (pinfunction "2_2") (pintype "passive"))
    )
    (net (code "88") (name "Net-(LED1-Pad4)") (class "Default")
      (node (ref "LED1") (pin "4") (pinfunction "4_4") (pintype "passive"))
      (node (ref "R52") (pin "2") (pinfunction "2_2") (pintype "passive"))
    )
    (net (code "89") (name "Net-(NTC1-2-PadP$2)") (class "Default")
      (node (ref "NTC1") (pin "P$2") (pinfunction "2_P$2") (pintype "passive"))
      (node (ref "NTC1") (pin "P$3") (pinfunction "2_P$3") (pintype "passive"))
      (node (ref "X1") (pin "1") (pinfunction "1_1") (pintype "passive"))
    )
    (net (code "90") (name "Net-(OC1-Pad2)") (class "Default")
      (node (ref "OC1") (pin "2") (pinfunction "2_2") (pintype "passive"))
      (node (ref "R74") (pin "2") (pinfunction "2_2") (pintype "passive"))
    )
    (net (code "91") (name "Net-(Q2-PadG)") (class "Default")
      (node (ref "Q2") (pin "G") (pinfunction "G_G") (pintype "passive"))
      (node (ref "R36") (pin "2") (pinfunction "2_2") (pintype "passive"))
      (node (ref "R38") (pin "1") (pinfunction "1_1") (pintype "passive"))
    )
    (net (code "92") (name "Net-(R2-Pad2)") (class "Default")
      (node (ref "R2") (pin "2") (pinfunction "2_2") (pintype "passive"))
      (node (ref "R3") (pin "2") (pinfunction "2_2") (pintype "passive"))
    )
    (net (code "93") (name "Net-(R3-Pad1)") (class "Default")
      (node (ref "R3") (pin "1") (pinfunction "1_1") (pintype "passive"))
      (node (ref "R4") (pin "1") (pinfunction "1_1") (pintype "passive"))
    )
    (net (code "94") (name "Net-(R7-Pad2)") (class "Default")
      (node (ref "R7") (pin "2") (pinfunction "2_2") (pintype "passive"))
      (node (ref "R8") (pin "1") (pinfunction "1_1") (pintype "passive"))
    )
    (net (code "95") (name "Net-(R10-Pad2)") (class "Default")
      (node (ref "R10") (pin "2") (pinfunction "2_2") (pintype "passive"))
      (node (ref "R9") (pin "1") (pinfunction "1_1") (pintype "passive"))
    )
    (net (code "96") (name "Net-(R11-Pad1)") (class "Default")
      (node (ref "R11") (pin "1") (pinfunction "1_1") (pintype "passive"))
      (node (ref "R12") (pin "1") (pinfunction "1_1") (pintype "passive"))
    )
    (net (code "97") (name "Net-(R20-Pad1)") (class "Default")
      (node (ref "R20") (pin "1") (pinfunction "1_1") (pintype "passive"))
      (node (ref "TRF1") (pin "15") (pinfunction "6_15") (pintype "passive"))
      (node (ref "TRF1") (pin "34") (pinfunction "6_34") (pintype "passive"))
      (node (ref "TRF1") (pin "5") (pinfunction "6_5") (pintype "passive"))
      (node (ref "TRF1") (pin "50") (pinfunction "6_50") (pintype "passive"))
    )
    (net (code "98") (name "Net-(R22-Pad2)") (class "Default")
      (node (ref "R22") (pin "2") (pinfunction "2_2") (pintype "passive"))
      (node (ref "TRF1") (pin "23") (pinfunction "11_23") (pintype "passive"))
      (node (ref "TRF1") (pin "28") (pinfunction "11_28") (pintype "passive"))
      (node (ref "TRF1") (pin "42") (pinfunction "11_42") (pintype "passive"))
      (node (ref "TRF1") (pin "8") (pinfunction "11_8") (pintype "passive"))
    )
    (net (code "99") (name "Net-(R27-Pad2)") (class "Default")
      (node (ref "R27") (pin "2") (pinfunction "2_2") (pintype "passive"))
      (node (ref "R30") (pin "1") (pinfunction "1_1") (pintype "passive"))
    )
    (net (code "100") (name "Net-(R30-Pad2)") (class "Default")
      (node (ref "R30") (pin "2") (pinfunction "2_2") (pintype "passive"))
      (node (ref "R33") (pin "1") (pinfunction "1_1") (pintype "passive"))
      (node (ref "R34") (pin "1") (pinfunction "1_1") (pintype "passive"))
    )
    (net (code "101") (name "Net-(R31-Pad2)") (class "Default")
      (node (ref "R31") (pin "2") (pinfunction "2_2") (pintype "passive"))
      (node (ref "R33") (pin "2") (pinfunction "2_2") (pintype "passive"))
      (node (ref "R34") (pin "2") (pinfunction "2_2") (pintype "passive"))
    )
    (net (code "102") (name "Net-(R54-Pad1)") (class "Default")
      (node (ref "R54") (pin "1") (pinfunction "1_1") (pintype "passive"))
      (node (ref "R59") (pin "2") (pinfunction "2_2") (pintype "passive"))
      (node (ref "R61") (pin "1") (pinfunction "1_1") (pintype "passive"))
      (node (ref "T3") (pin "E") (pinfunction "E_E") (pintype "passive"))
    )
    (net (code "103") (name "Net-(R54-Pad2)") (class "Default")
      (node (ref "R54") (pin "2") (pinfunction "2_2") (pintype "passive"))
      (node (ref "R55") (pin "1") (pinfunction "1_1") (pintype "passive"))
      (node (ref "T3") (pin "B") (pinfunction "B_B") (pintype "passive"))
    )
    (net (code "104") (name "Net-(R59-Pad1)") (class "Default")
      (node (ref "R59") (pin "1") (pinfunction "1_1") (pintype "passive"))
      (node (ref "R60") (pin "1") (pinfunction "1_1") (pintype "passive"))
      (node (ref "T3") (pin "C") (pinfunction "C_C") (pintype "passive"))
    )
    (net (code "105") (name "Net-(R63-Pad1)") (class "Default")
      (node (ref "R63") (pin "1") (pinfunction "1_1") (pintype "passive"))
      (node (ref "R64") (pin "2") (pinfunction "2_2") (pintype "passive"))
    )
    (net (code "106") (name "Net-(R85-Pad2)") (class "Default")
      (node (ref "R85") (pin "2") (pinfunction "2_2") (pintype "passive"))
      (node (ref "X2") (pin "VBUS") (pinfunction "VBUS_VBUS") (pintype "bidirectional"))
    )
    (net (code "107") (name "Net-(R112-Pad1)") (class "Default")
      (node (ref "R112") (pin "1") (pinfunction "1_1") (pintype "passive"))
      (node (ref "R115") (pin "1") (pinfunction "1_1") (pintype "passive"))
    )
    (net (code "108") (name "Net-(R115-Pad2)") (class "Default")
      (node (ref "R115") (pin "2") (pinfunction "2_2") (pintype "passive"))
      (node (ref "T10") (pin "C") (pinfunction "C_C") (pintype "passive"))
    )
    (net (code "109") (name "Net-(R133-Pad1)") (class "Default")
      (node (ref "R133") (pin "1") (pinfunction "1_1") (pintype "passive"))
      (node (ref "R134") (pin "2") (pinfunction "2_2") (pintype "passive"))
    )
    (net (code "110") (name "Net-(T1-B)") (class "Default")
      (node (ref "R7") (pin "1") (pinfunction "1_1") (pintype "passive"))
      (node (ref "T1") (pin "1") (pinfunction "B_1") (pintype "passive"))
      (node (ref "T1_X") (pin "1") (pinfunction "B_1") (pintype "passive"))
      (node (ref "Z1") (pin "3") (pinfunction "C_3") (pintype "passive"))
    )
    (net (code "111") (name "Net-(T1-C)") (class "Default")
      (node (ref "C13") (pin "+") (pinfunction "+_+") (pintype "passive"))
      (node (ref "C29") (pin "2") (pinfunction "2_2") (pintype "passive"))
      (node (ref "R13") (pin "1") (pinfunction "1_1") (pintype "passive"))
      (node (ref "R8") (pin "2") (pinfunction "2_2") (pintype "passive"))
      (node (ref "T1") (pin "4") (pinfunction "C_4") (pintype "passive"))
      (node (ref "T1_X") (pin "3") (pinfunction "C_3") (pintype "passive"))
    )
    (net (code "112") (name "Net-(T1-E)") (class "Default")
      (node (ref "C10") (pin "+") (pinfunction "+_+") (pintype "passive"))
      (node (ref "R16") (pin "1") (pinfunction "1_1") (pintype "passive"))
      (node (ref "T1") (pin "3") (pinfunction "E_3") (pintype "passive"))
      (node (ref "T1_X") (pin "2") (pinfunction "E_2") (pintype "passive"))
    )
    (net (code "113") (name "Net-(T4-B)") (class "Default")
      (node (ref "C60") (pin "2") (pinfunction "2_2") (pintype "passive"))
      (node (ref "R82") (pin "1") (pinfunction "1_1") (pintype "passive"))
      (node (ref "R84") (pin "2") (pinfunction "2_2") (pintype "passive"))
      (node (ref "T4") (pin "1") (pinfunction "B_1") (pintype "passive"))
    )
    (net (code "114") (name "Net-(T4-C)") (class "Default")
      (node (ref "R78") (pin "1") (pinfunction "1_1") (pintype "passive"))
      (node (ref "R79") (pin "2") (pinfunction "2_2") (pintype "passive"))
      (node (ref "T4") (pin "3") (pinfunction "C_3") (pintype "passive"))
    )
    (net (code "115") (name "Net-(T4-E)") (class "Default")
      (node (ref "R81") (pin "1") (pinfunction "1_1") (pintype "passive"))
      (node (ref "T4") (pin "2") (pinfunction "E_2") (pintype "passive"))
    )
    (net (code "116") (name "Net-(T5-B)") (class "Default")
      (node (ref "R86") (pin "1") (pinfunction "1_1") (pintype "passive"))
      (node (ref "R87") (pin "2") (pinfunction "2_2") (pintype "passive"))
      (node (ref "T5") (pin "1") (pinfunction "B_1") (pintype "passive"))
    )
    (net (code "117") (name "Net-(T5-C)") (class "Default")
      (node (ref "D10") (pin "A") (pinfunction "A_A") (pintype "passive"))
      (node (ref "RL1") (pin "1") (pinfunction "1_1") (pintype "passive"))
      (node (ref "T5") (pin "3") (pinfunction "C_3") (pintype "passive"))
    )
    (net (code "118") (name "Net-(T6-B)") (class "Default")
      (node (ref "R95") (pin "1") (pinfunction "1_1") (pintype "passive"))
      (node (ref "R99") (pin "2") (pinfunction "2_2") (pintype "passive"))
      (node (ref "T6") (pin "1") (pinfunction "B_1") (pintype "passive"))
    )
    (net (code "119") (name "Net-(T6-C)") (class "Default")
      (node (ref "R104") (pin "1") (pinfunction "1_1") (pintype "passive"))
      (node (ref "T6") (pin "3") (pinfunction "C_3") (pintype "passive"))
      (node (ref "Z6") (pin "3") (pinfunction "C_3") (pintype "passive"))
    )
    (net (code "120") (name "Net-(T7-B)") (class "Default")
      (node (ref "R109") (pin "1") (pinfunction "1_1") (pintype "passive"))
      (node (ref "T7") (pin "1") (pinfunction "B_1") (pintype "passive"))
    )
    (net (code "121") (name "Net-(T9-B)") (class "Default")
      (node (ref "R113") (pin "1") (pinfunction "1_1") (pintype "passive"))
      (node (ref "R114") (pin "1") (pinfunction "1_1") (pintype "passive"))
      (node (ref "T9") (pin "1") (pinfunction "B_1") (pintype "passive"))
    )
    (net (code "122") (name "Net-(TRF1-2-Pad1)") (class "Default")
      (node (ref "TRF1") (pin "1") (pinfunction "2_1") (pintype "passive"))
      (node (ref "TRF1") (pin "17") (pinfunction "3_17") (pintype "passive"))
      (node (ref "TRF1") (pin "18") (pinfunction "2_18") (pintype "passive"))
      (node (ref "TRF1") (pin "2") (pinfunction "3_2") (pintype "passive"))
      (node (ref "TRF1") (pin "36") (pinfunction "3_36") (pintype "passive"))
      (node (ref "TRF1") (pin "37") (pinfunction "2_37") (pintype "passive"))
      (node (ref "TRF1") (pin "53") (pinfunction "3_53") (pintype "passive"))
      (node (ref "TRF1") (pin "54") (pinfunction "2_54") (pintype "passive"))
    )
    (net (code "123") (name "Net-(U1-BOOT0)") (class "Default")
      (node (ref "R56") (pin "2") (pinfunction "2_2") (pintype "passive"))
      (node (ref "U1") (pin "44") (pinfunction "BOOT0_44") (pintype "bidirectional"))
    )
    (net (code "124") (name "Net-(U1-PB15)") (class "Default")
      (node (ref "TP4") (pin "TP") (pinfunction "TP_TP") (pintype "input"))
      (node (ref "U1") (pin "28") (pinfunction "PB15_28") (pintype "bidirectional"))
    )
    (net (code "125") (name "Net-(U1-VDDA)") (class "Default")
      (node (ref "C31") (pin "1") (pinfunction "1_1") (pintype "passive"))
      (node (ref "C32") (pin "1") (pinfunction "1_1") (pintype "passive"))
      (node (ref "R45") (pin "1") (pinfunction "1_1") (pintype "passive"))
      (node (ref "U1") (pin "9") (pinfunction "VDDA_9") (pintype "bidirectional"))
    )
    (net (code "126") (name "Net-(U2-BS)") (class "Default")
      (node (ref "R194") (pin "1") (pinfunction "1_1") (pintype "passive"))
      (node (ref "U2") (pin "1") (pinfunction "BS_1") (pintype "bidirectional"))
    )
    (net (code "127") (name "Net-(U2-EN)") (class "Default")
      (node (ref "R193") (pin "1") (pinfunction "1_1") (pintype "passive"))
      (node (ref "U2") (pin "4") (pinfunction "EN_4") (pintype "bidirectional"))
    )
    (net (code "128") (name "Net-(X3C-1)") (class "Default")
      (node (ref "RL1") (pin "P0") (pinfunction "P0_P0") (pintype "passive"))
      (node (ref "RL1") (pin "P1") (pinfunction "P1_P1") (pintype "passive"))
      (node (ref "X3") (pin "3") (pinfunction "1_3") (pintype "passive"))
    )
    (net (code "129") (name "Net-(X3D-1)") (class "Default")
      (node (ref "RL1") (pin "S0") (pinfunction "S0_S0") (pintype "passive"))
      (node (ref "X3") (pin "4") (pinfunction "1_4") (pintype "passive"))
    )
    (net (code "130") (name "Net-(X4B-1)") (class "Default")
      (node (ref "R94") (pin "1") (pinfunction "1_1") (pintype "passive"))
      (node (ref "X4") (pin "2") (pinfunction "1_2") (pintype "passive"))
    )
    (net (code "131") (name "Net-(X4C-1)") (class "Default")
      (node (ref "D11") (pin "C") (pinfunction "C_C") (pintype "passive"))
      (node (ref "X4") (pin "3") (pinfunction "1_3") (pintype "passive"))
    )
    (net (code "132") (name "Net-(Z4-C)") (class "Default")
      (node (ref "R91") (pin "2") (pinfunction "2_2") (pintype "passive"))
      (node (ref "R92") (pin "2") (pinfunction "2_2") (pintype "passive"))
      (node (ref "R93") (pin "2") (pinfunction "2_2") (pintype "passive"))
      (node (ref "Z4") (pin "3") (pinfunction "C_3") (pintype "passive"))
    )
    (net (code "133") (name "Net-(Z5-A)") (class "Default")
      (node (ref "R103") (pin "2") (pinfunction "2_2") (pintype "passive"))
      (node (ref "Z5") (pin "1") (pinfunction "A_1") (pintype "passive"))
    )
    (net (code "134") (name "Net-(Z5-C)") (class "Default")
      (node (ref "OC2") (pin "2") (pinfunction "2_2") (pintype "passive"))
      (node (ref "Z5") (pin "3") (pinfunction "C_3") (pintype "passive"))
    )
    (net (code "135") (name "Net-(Z7-C)") (class "Default")
      (node (ref "D14") (pin "C") (pinfunction "C_C") (pintype "passive"))
      (node (ref "R112") (pin "2") (pinfunction "2_2") (pintype "passive"))
      (node (ref "R113") (pin "2") (pinfunction "2_2") (pintype "passive"))
      (node (ref "Z7") (pin "3") (pinfunction "C_3") (pintype "passive"))
    )
    (net (code "136") (name "OVER_VOLT") (class "Default")
      (node (ref "R95") (pin "2") (pinfunction "2_2") (pintype "passive"))
      (node (ref "U1") (pin "38") (pinfunction "PA15_38") (pintype "bidirectional"))
    )
    (net (code "137") (name "PT100_ADC") (class "Default")
      (node (ref "C70") (pin "2") (pinfunction "2_2") (pintype "passive"))
      (node (ref "D13") (pin "3") (pinfunction "AC_3") (pintype "passive"))
      (node (ref "R108") (pin "2") (pinfunction "2_2") (pintype "passive"))
      (node (ref "U1") (pin "11") (pinfunction "PA1_11") (pintype "bidirectional"))
    )
    (net (code "138") (name "RELAY_OP") (class "Default")
      (node (ref "R86") (pin "2") (pinfunction "2_2") (pintype "passive"))
      (node (ref "U1") (pin "12") (pinfunction "PA2_12") (pintype "bidirectional"))
    )
    (net (code "139") (name "SWCLK") (class "Default")
      (node (ref "PROG1") (pin "2") (pinfunction "PRG_SWCLK_2") (pintype "passive"))
      (node (ref "PROG2") (pin "2") (pinfunction "PRG_SWCLK_2") (pintype "passive"))
      (node (ref "U1") (pin "37") (pinfunction "PA14_37") (pintype "bidirectional"))
    )
    (net (code "140") (name "SWDIO") (class "Default")
      (node (ref "PROG1") (pin "4") (pinfunction "PRG_SWDIO_4") (pintype "passive"))
      (node (ref "PROG2") (pin "4") (pinfunction "PRG_SWDIO_4") (pintype "passive"))
      (node (ref "U1") (pin "34") (pinfunction "PA13_34") (pintype "bidirectional"))
    )
    (net (code "141") (name "USB_DM") (class "Default")
      (node (ref "C66") (pin "1") (pinfunction "1_1") (pintype "passive"))
      (node (ref "R97") (pin "2") (pinfunction "2_2") (pintype "passive"))
      (node (ref "U1") (pin "32") (pinfunction "PA11_32") (pintype "bidirectional"))
    )
    (net (code "142") (name "USB_DP") (class "Default")
      (node (ref "C67") (pin "1") (pinfunction "1_1") (pintype "passive"))
      (node (ref "R100") (pin "1") (pinfunction "1_1") (pintype "passive"))
      (node (ref "R96") (pin "2") (pinfunction "2_2") (pintype "passive"))
      (node (ref "U1") (pin "33") (pinfunction "PA12_33") (pintype "bidirectional"))
    )
    (net (code "143") (name "VBAT_ADC") (class "Default")
      (node (ref "C44") (pin "1") (pinfunction "1_1") (pintype "passive"))
      (node (ref "R57") (pin "2") (pinfunction "2_2") (pintype "passive"))
      (node (ref "R58") (pin "1") (pinfunction "1_1") (pintype "passive"))
      (node (ref "U1") (pin "13") (pinfunction "PA3_13") (pintype "bidirectional"))
    )
    (net (code "144") (name "VOUT+_ADC") (class "Default")
      (node (ref "C41") (pin "1") (pinfunction "1_1") (pintype "passive"))
      (node (ref "R50") (pin "2") (pinfunction "2_2") (pintype "passive"))
      (node (ref "R51") (pin "1") (pinfunction "1_1") (pintype "passive"))
      (node (ref "U1") (pin "14") (pinfunction "PA4_14") (pintype "bidirectional"))
    )
    (net (code "145") (name "V_NTC_ADC") (class "Default")
      (node (ref "C53") (pin "1") (pinfunction "1_1") (pintype "passive"))
      (node (ref "R72") (pin "1") (pinfunction "1_1") (pintype "passive"))
      (node (ref "R73") (pin "1") (pinfunction "1_1") (pintype "passive"))
      (node (ref "U1") (pin "10") (pinfunction "PA0_10") (pintype "bidirectional"))
    )
    (net (code "146") (name "V_PWM") (class "Default")
      (node (ref "R84") (pin "1") (pinfunction "1_1") (pintype "passive"))
      (node (ref "U1") (pin "19") (pinfunction "PB1_19") (pintype "bidirectional"))
    )
    (net (code "147") (name "unconnected-(U1-PA8-Pad29)") (class "Default")
      (node (ref "U1") (pin "29") (pinfunction "PA8_29") (pintype "bidirectional"))
    )
    (net (code "148") (name "unconnected-(U1-PA9-Pad30)") (class "Default")
      (node (ref "U1") (pin "30") (pinfunction "PA9_30") (pintype "bidirectional"))
    )
    (net (code "149") (name "unconnected-(U1-PA10-Pad31)") (class "Default")
      (node (ref "U1") (pin "31") (pinfunction "PA10_31") (pintype "bidirectional"))
    )
    (net (code "150") (name "unconnected-(U1-PB2-Pad20)") (class "Default")
      (node (ref "U1") (pin "20") (pinfunction "PB2_20") (pintype "bidirectional"))
    )
    (net (code "151") (name "unconnected-(U1-PB7-Pad43)") (class "Default")
      (node (ref "U1") (pin "43") (pinfunction "PB7_43") (pintype "bidirectional"))
    )
    (net (code "152") (name "unconnected-(U1-PB8-Pad45)") (class "Default")
      (node (ref "U1") (pin "45") (pinfunction "PB8_45") (pintype "bidirectional"))
    )
    (net (code "153") (name "unconnected-(U1-PB9-Pad46)") (class "Default")
      (node (ref "U1") (pin "46") (pinfunction "PB9_46") (pintype "bidirectional"))
    )
    (net (code "154") (name "unconnected-(U1-PB10-Pad21)") (class "Default")
      (node (ref "U1") (pin "21") (pinfunction "PB10_21") (pintype "bidirectional"))
    )
    (net (code "155") (name "unconnected-(U1-PB11-Pad22)") (class "Default")
      (node (ref "U1") (pin "22") (pinfunction "PB11_22") (pintype "bidirectional"))
    )
    (net (code "156") (name "unconnected-(U1-PB12-Pad25)") (class "Default")
      (node (ref "U1") (pin "25") (pinfunction "PB12_25") (pintype "bidirectional"))
    )
    (net (code "157") (name "unconnected-(U1-PB13-Pad26)") (class "Default")
      (node (ref "U1") (pin "26") (pinfunction "PB13_26") (pintype "bidirectional"))
    )
    (net (code "158") (name "unconnected-(U1-PB14-Pad27)") (class "Default")
      (node (ref "U1") (pin "27") (pinfunction "PB14_27") (pintype "bidirectional"))
    )
    (net (code "159") (name "unconnected-(U1-PC13-Pad2)") (class "Default")
      (node (ref "U1") (pin "2") (pinfunction "PC13_2") (pintype "bidirectional"))
    )
    (net (code "160") (name "unconnected-(U1-PC14{slash}OSC32_IN-Pad3)") (class "Default")
      (node (ref "U1") (pin "3") (pinfunction "PC14/OSC32_IN_3") (pintype "bidirectional"))
    )
    (net (code "161") (name "unconnected-(U1-PC15{slash}OSC32_OUT-Pad4)") (class "Default")
      (node (ref "U1") (pin "4") (pinfunction "PC15/OSC32_OUT_4") (pintype "bidirectional"))
    )
    (net (code "162") (name "unconnected-(U1-VBAT-Pad1)") (class "Default")
      (node (ref "U1") (pin "1") (pinfunction "VBAT_1") (pintype "bidirectional"))
    )
  )
)
